# 612_jetracer_328_211.net
KiCad netlist of a schematic drawn in EAGLE
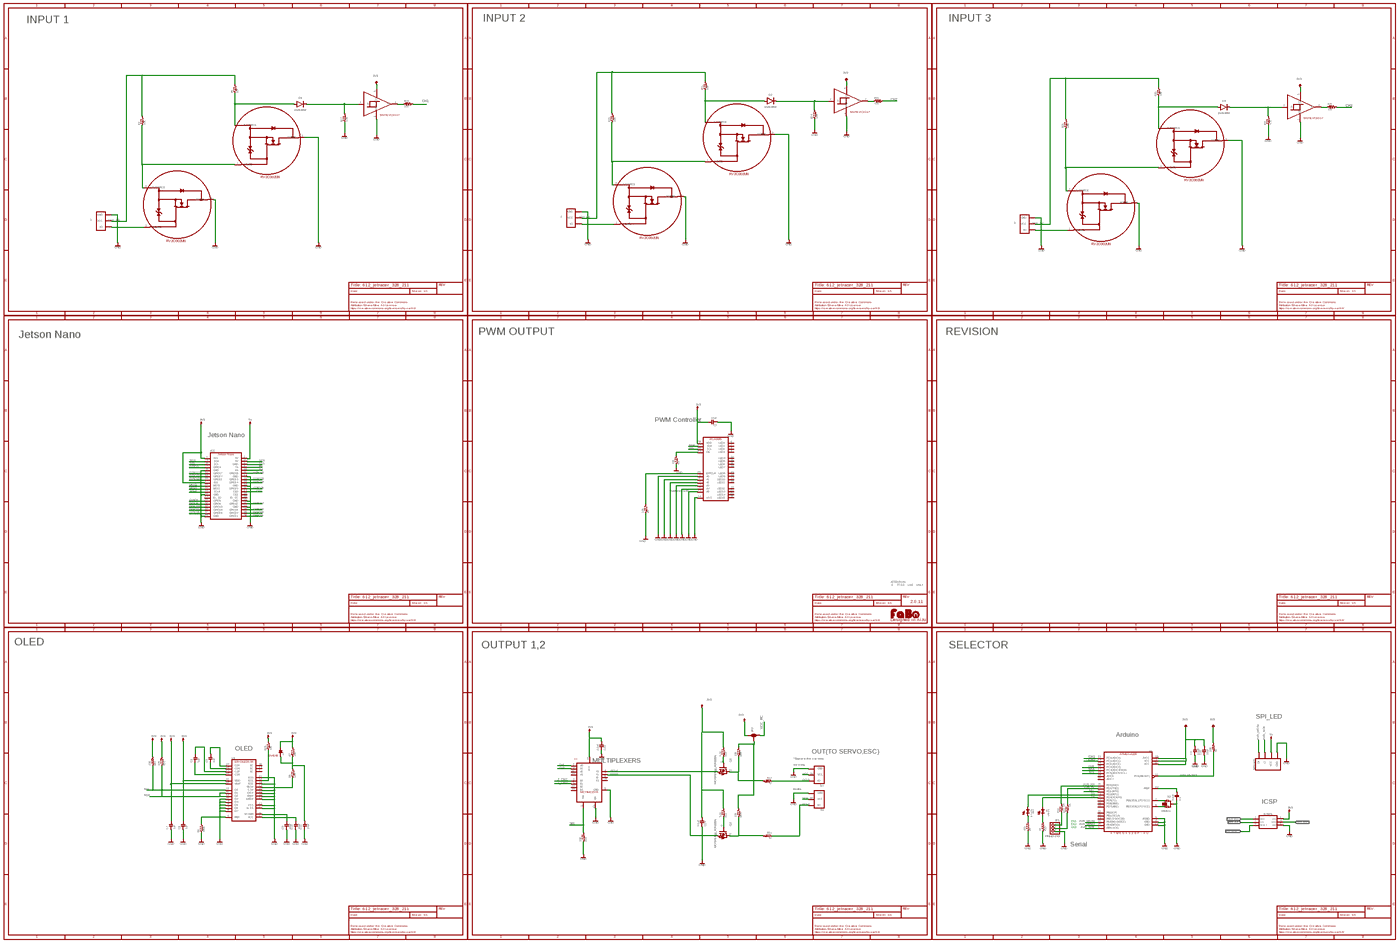
[diagram p0: schematic, sheet 1, overview]
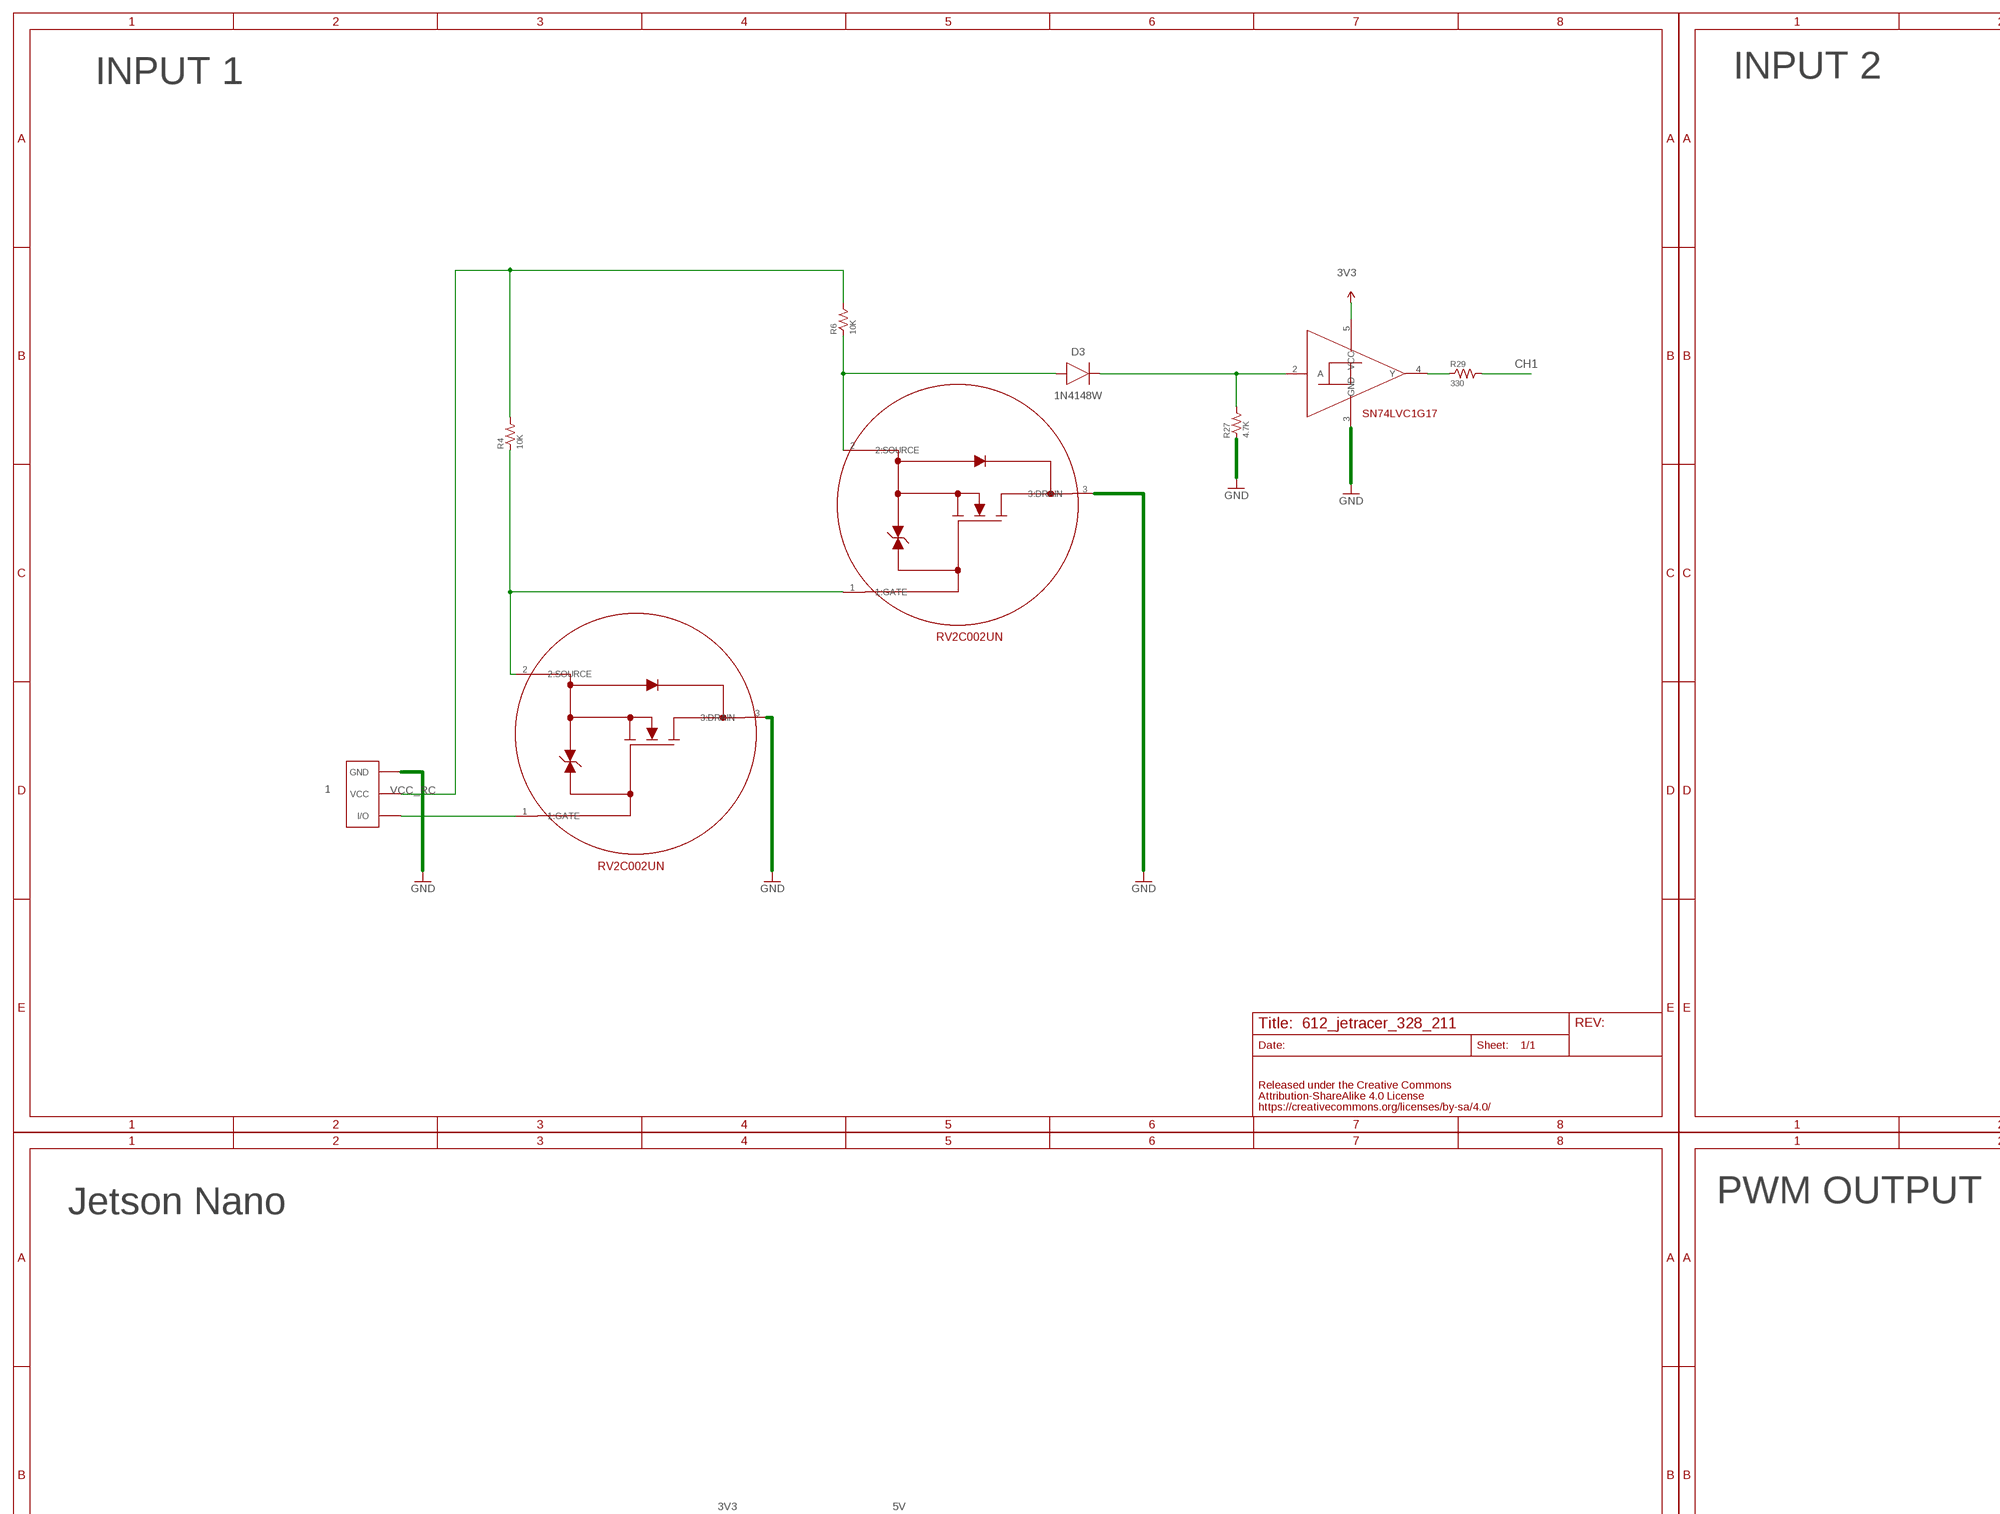
[diagram p1: schematic, sheet 1, part 1 of 6]
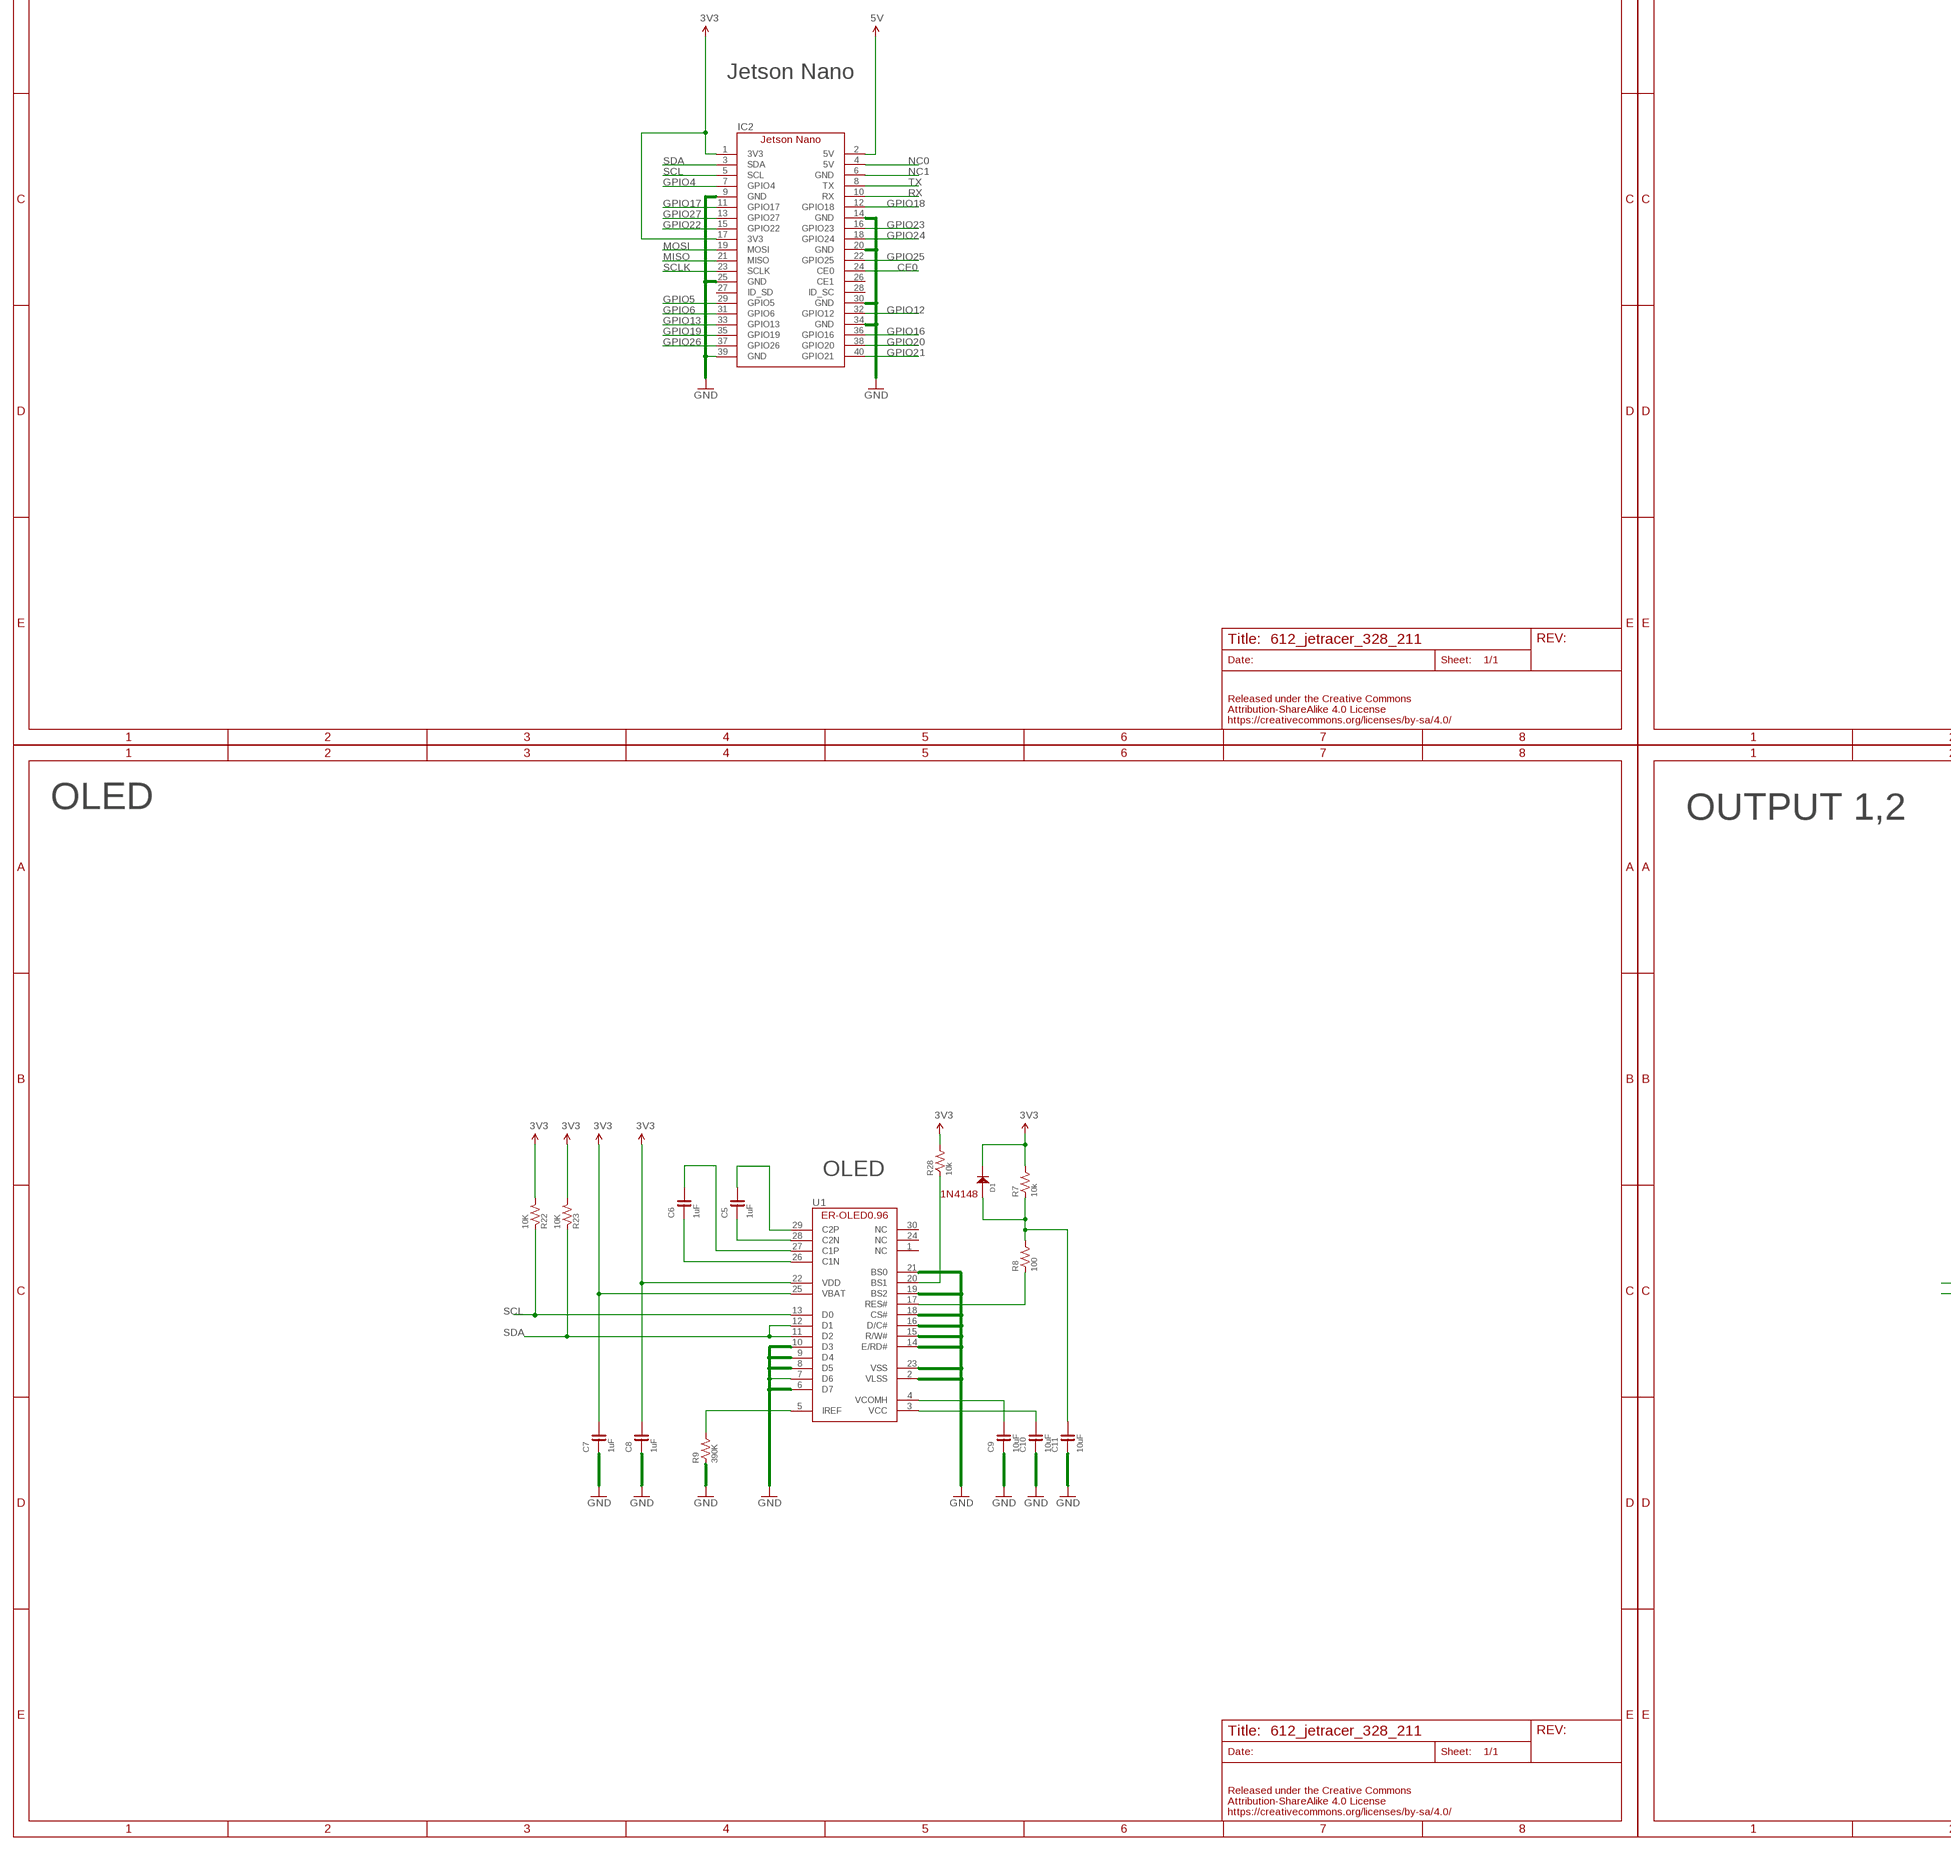
[diagram p2: schematic, sheet 1, part 2 of 6]
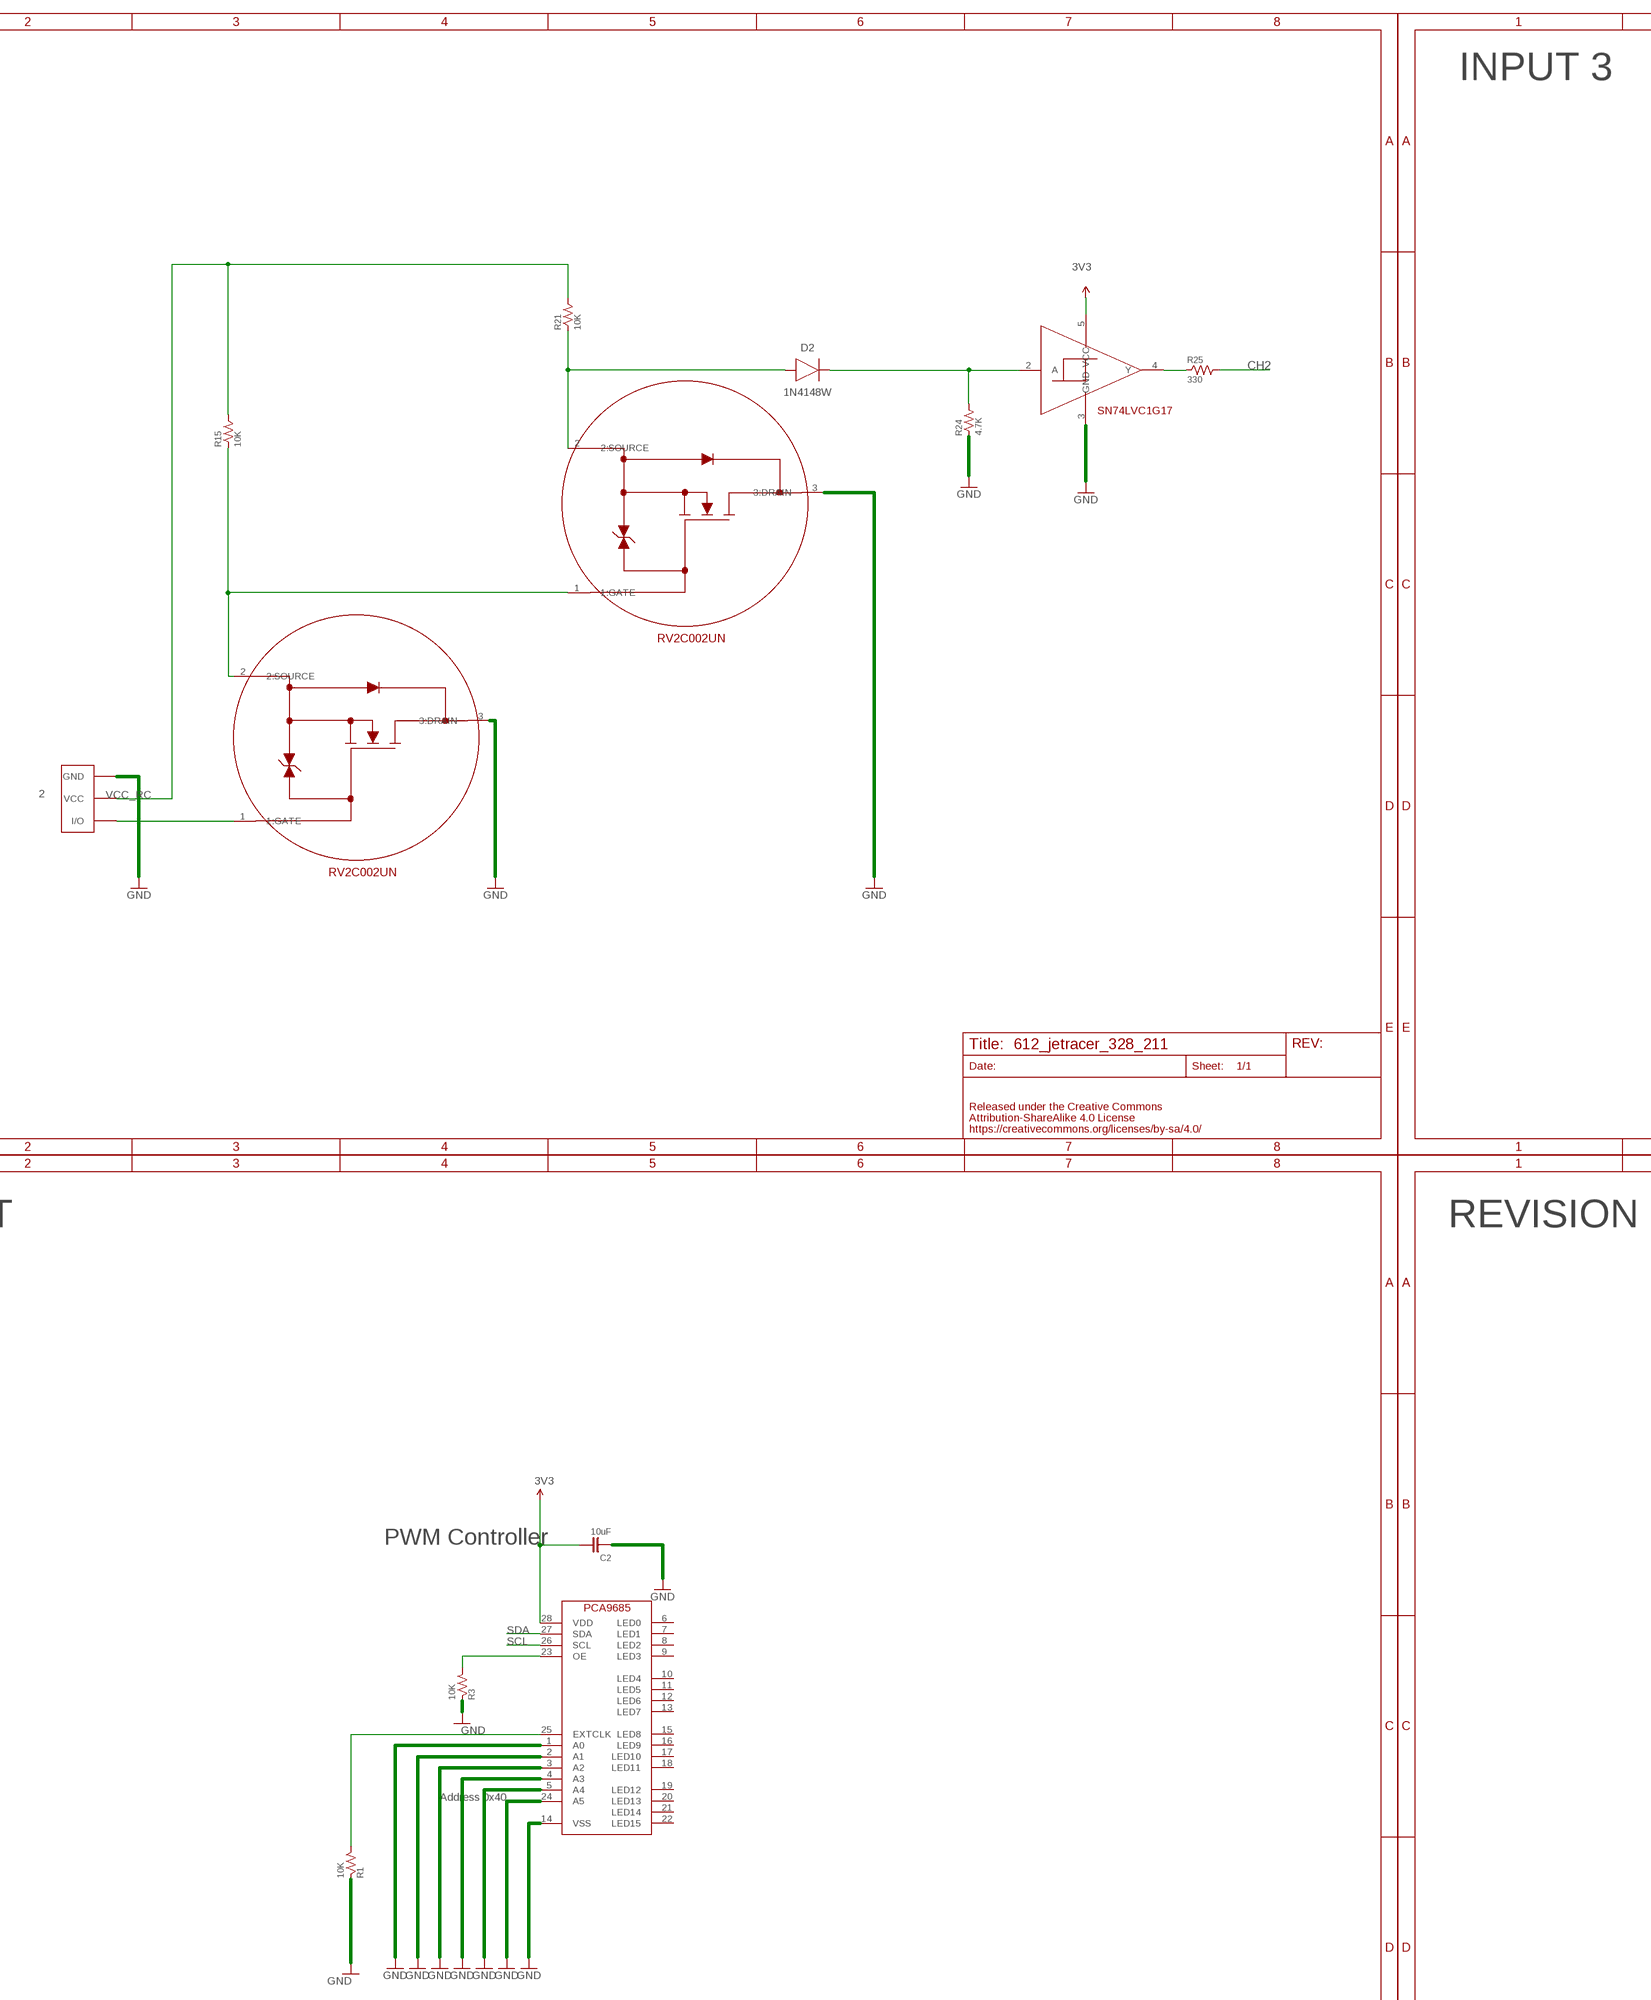
[diagram p3: schematic, sheet 1, part 3 of 6]
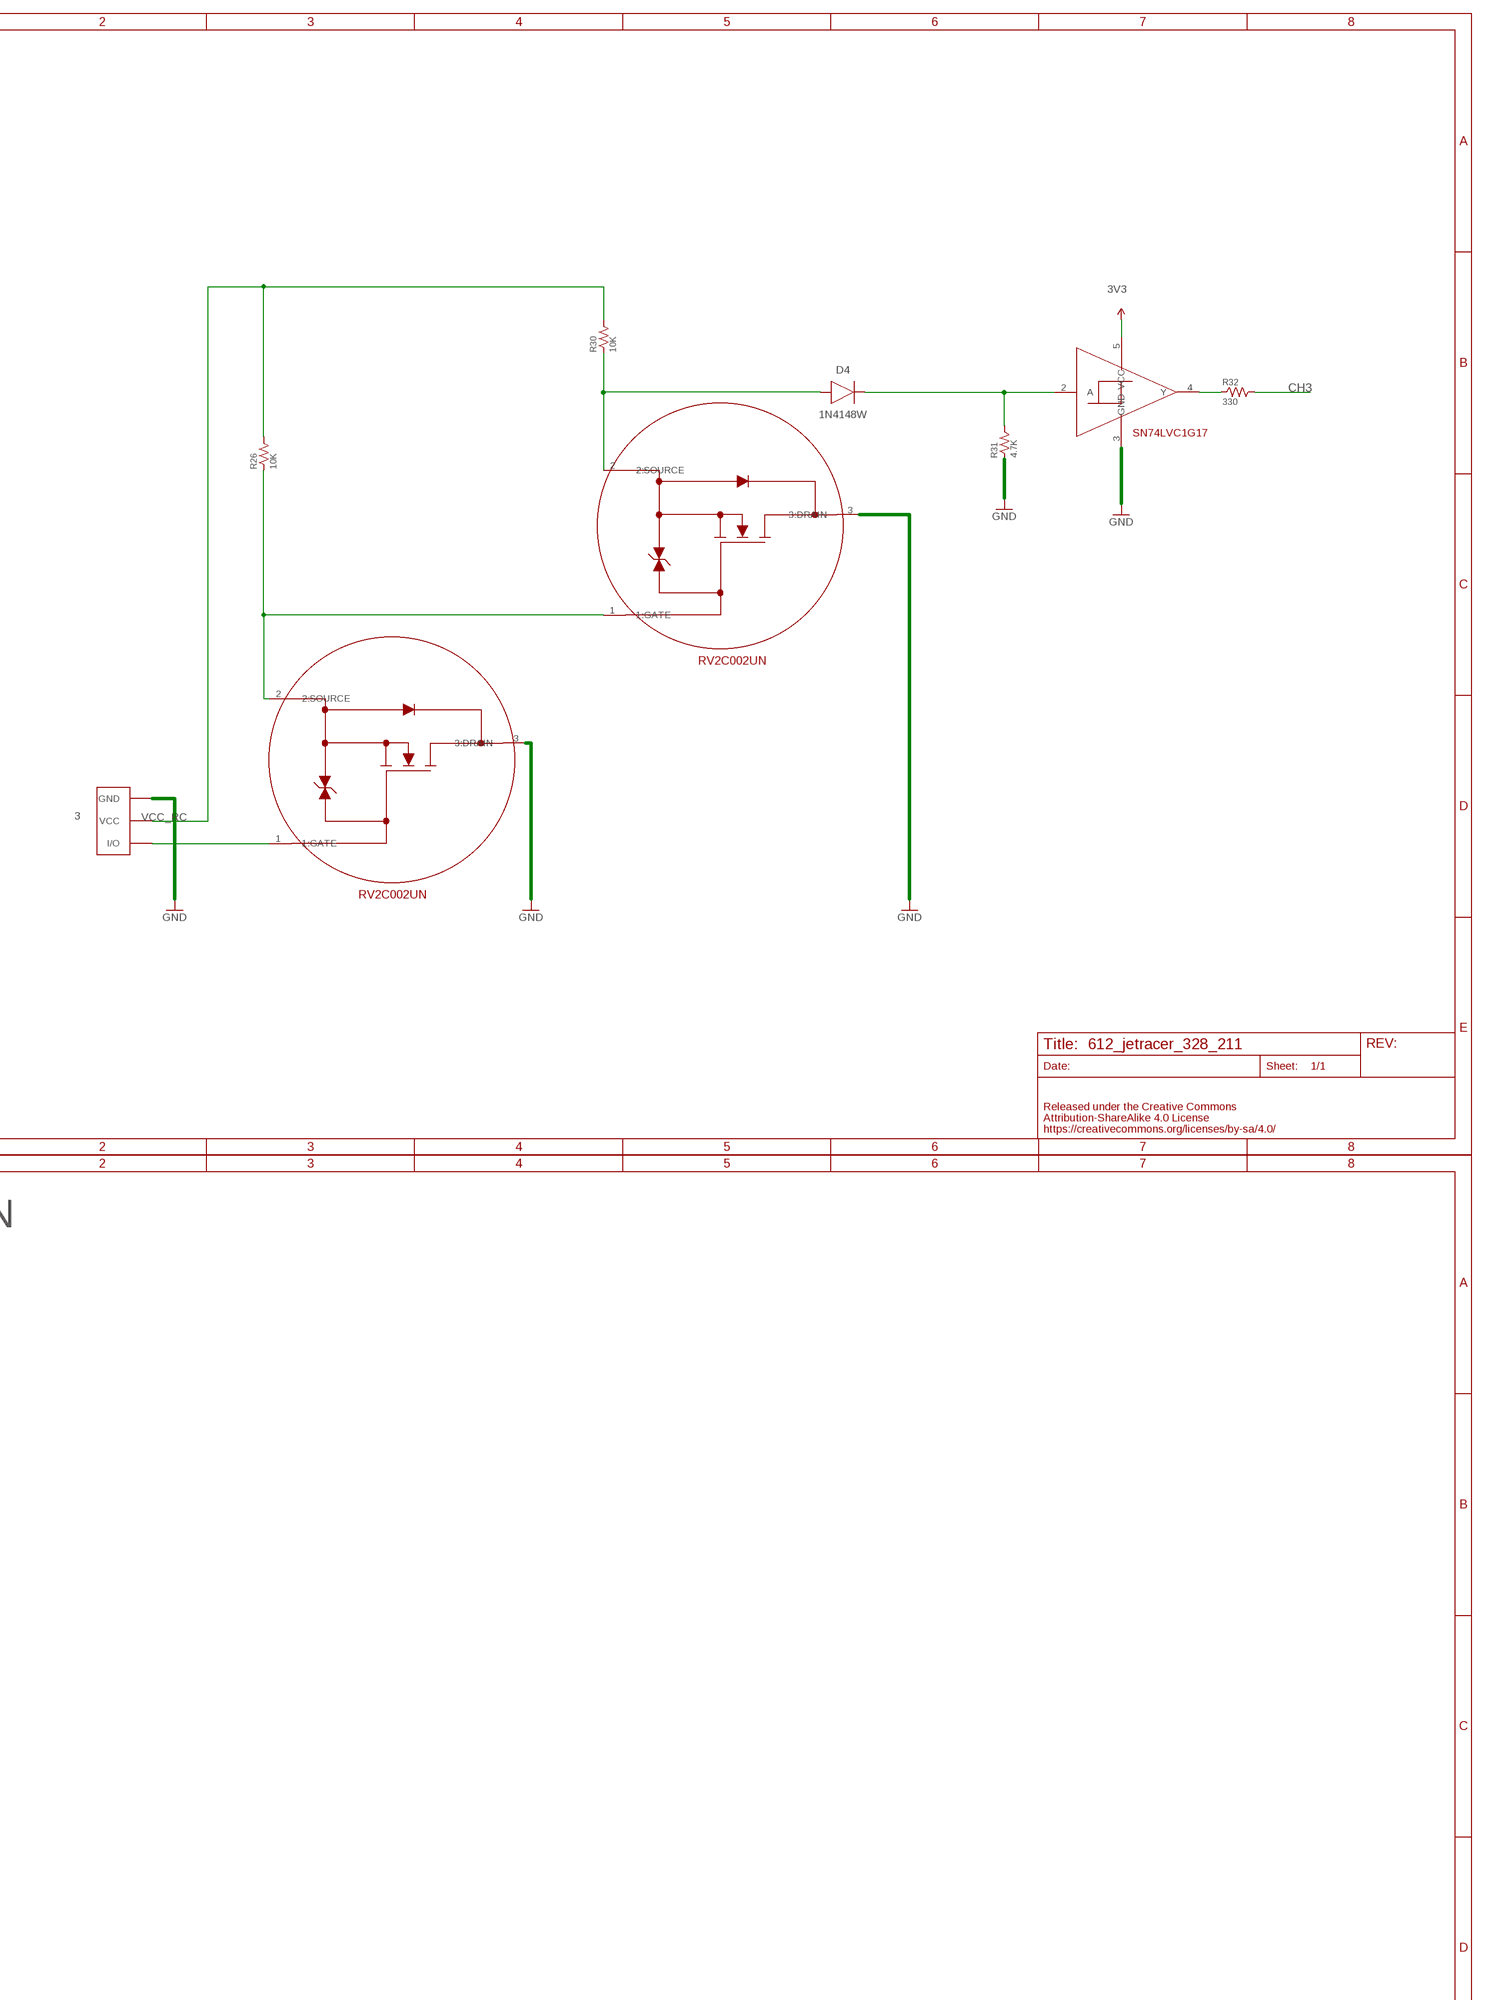
[diagram p4: schematic, sheet 1, part 4 of 6]
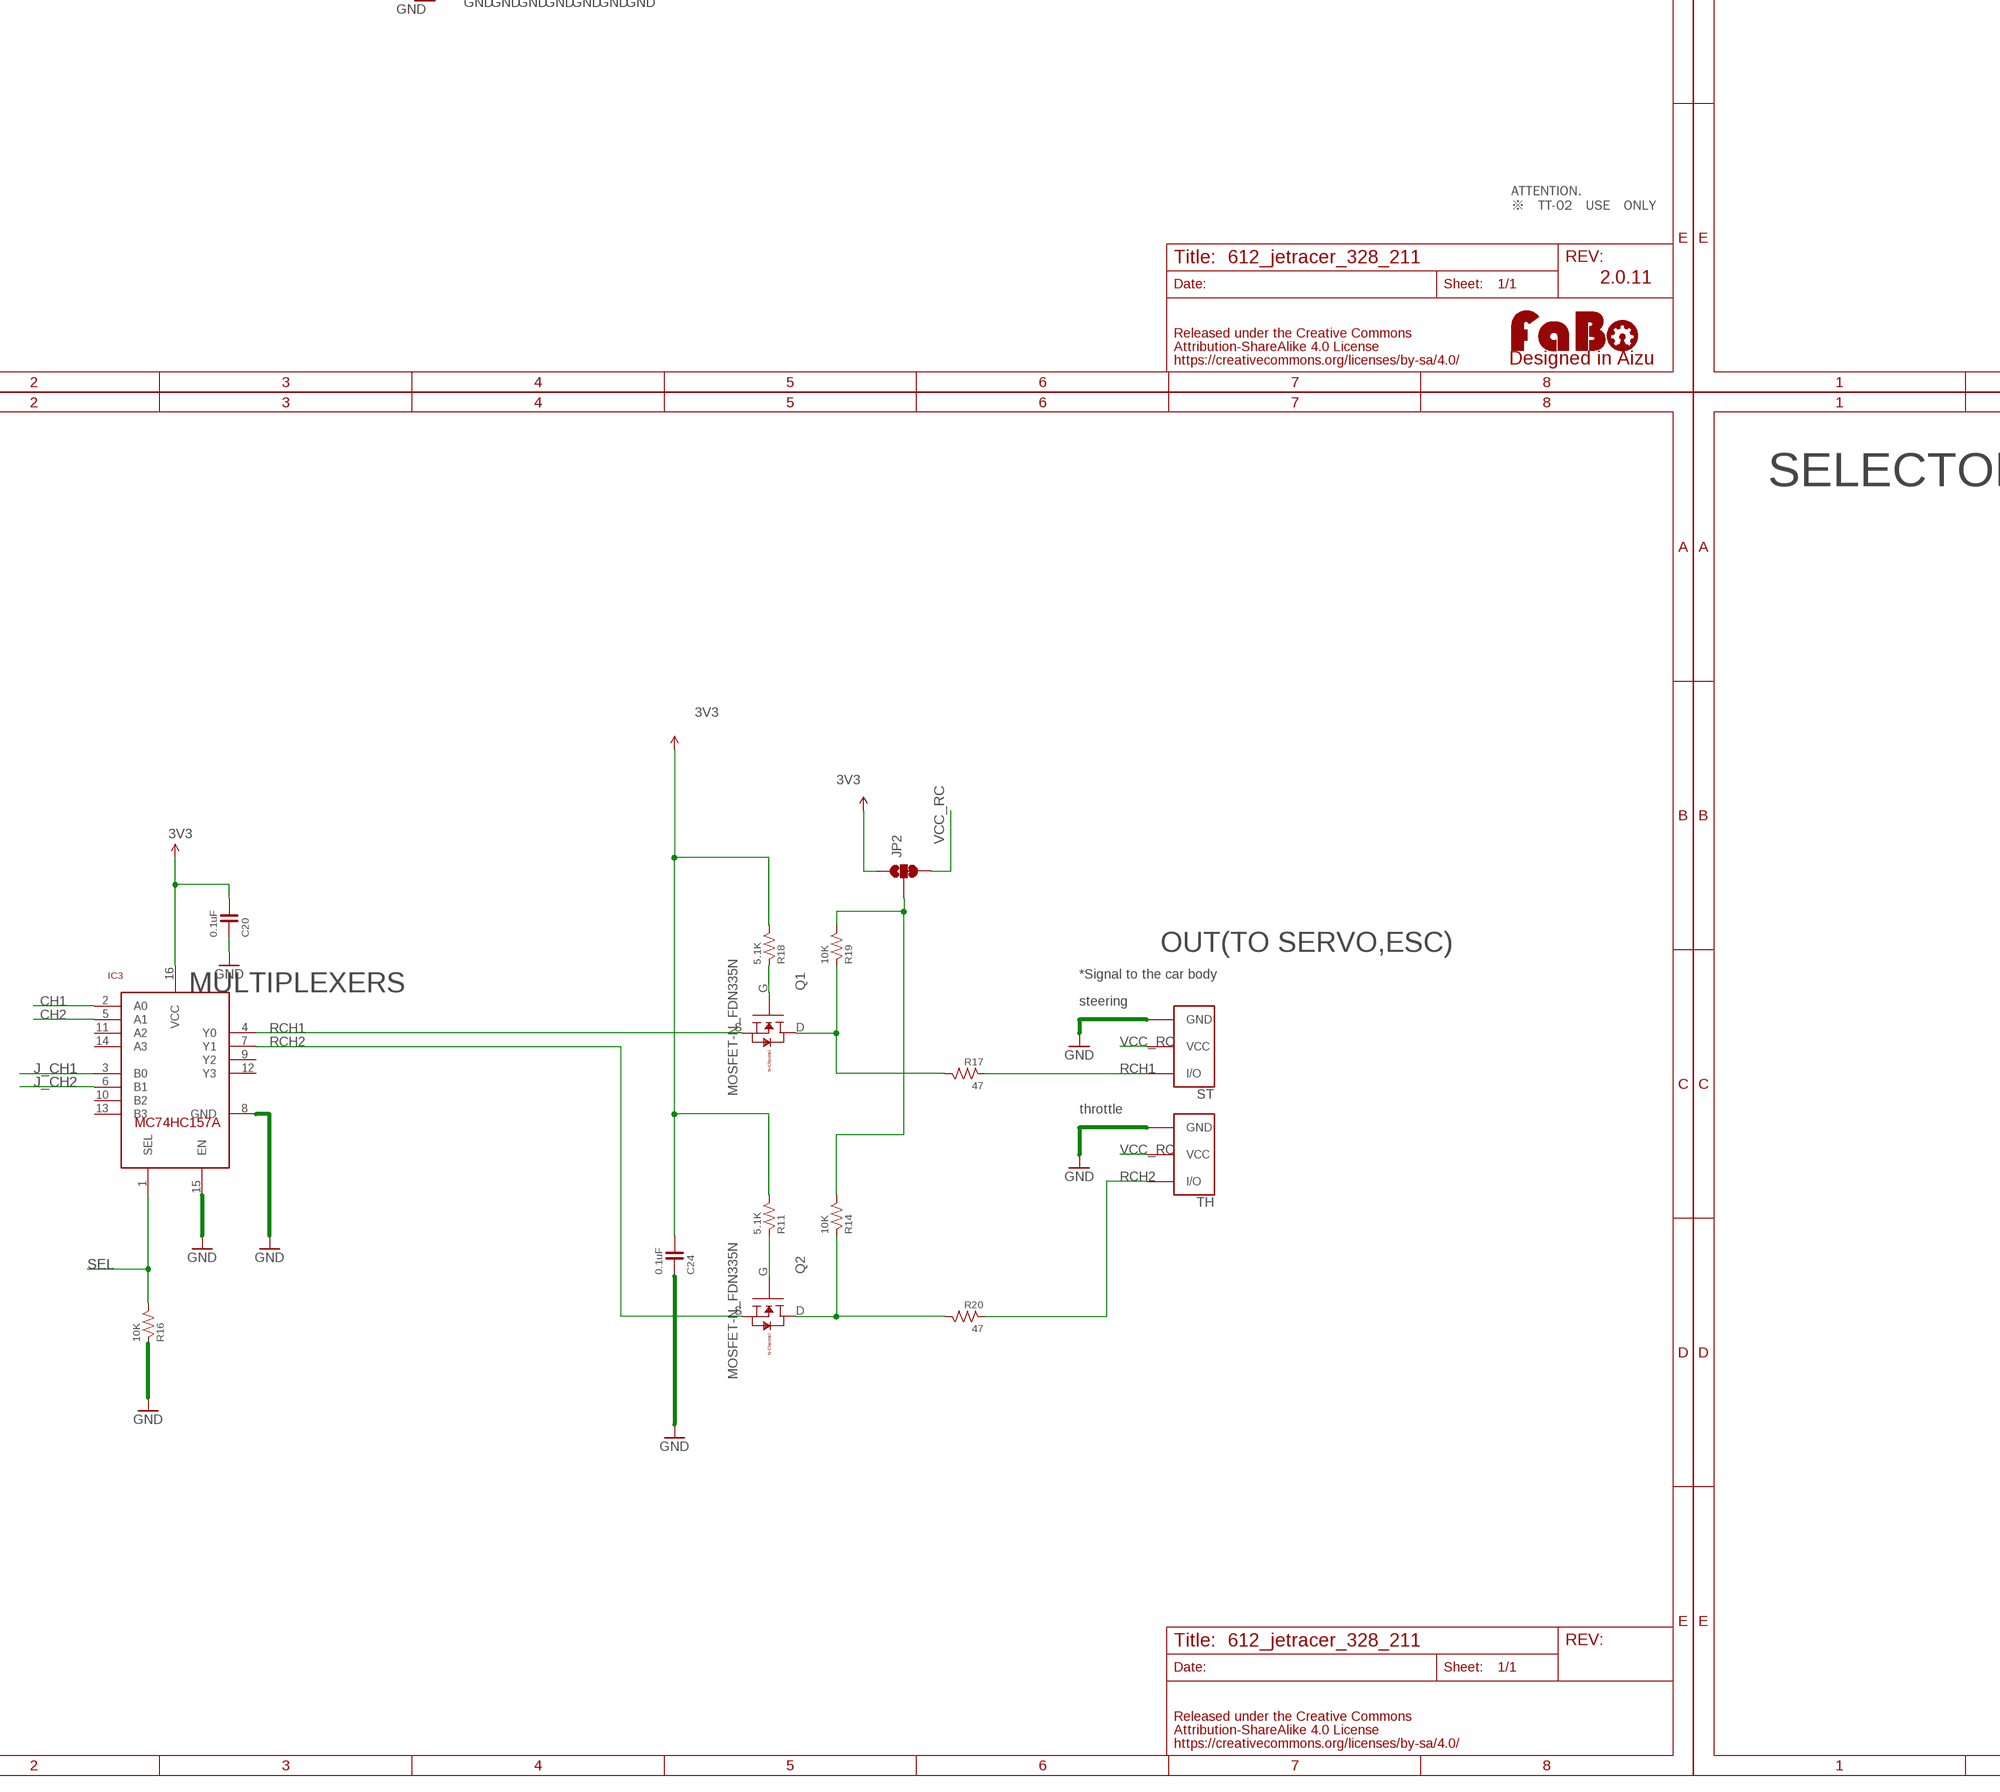
[diagram p5: schematic, sheet 1, part 5 of 6]
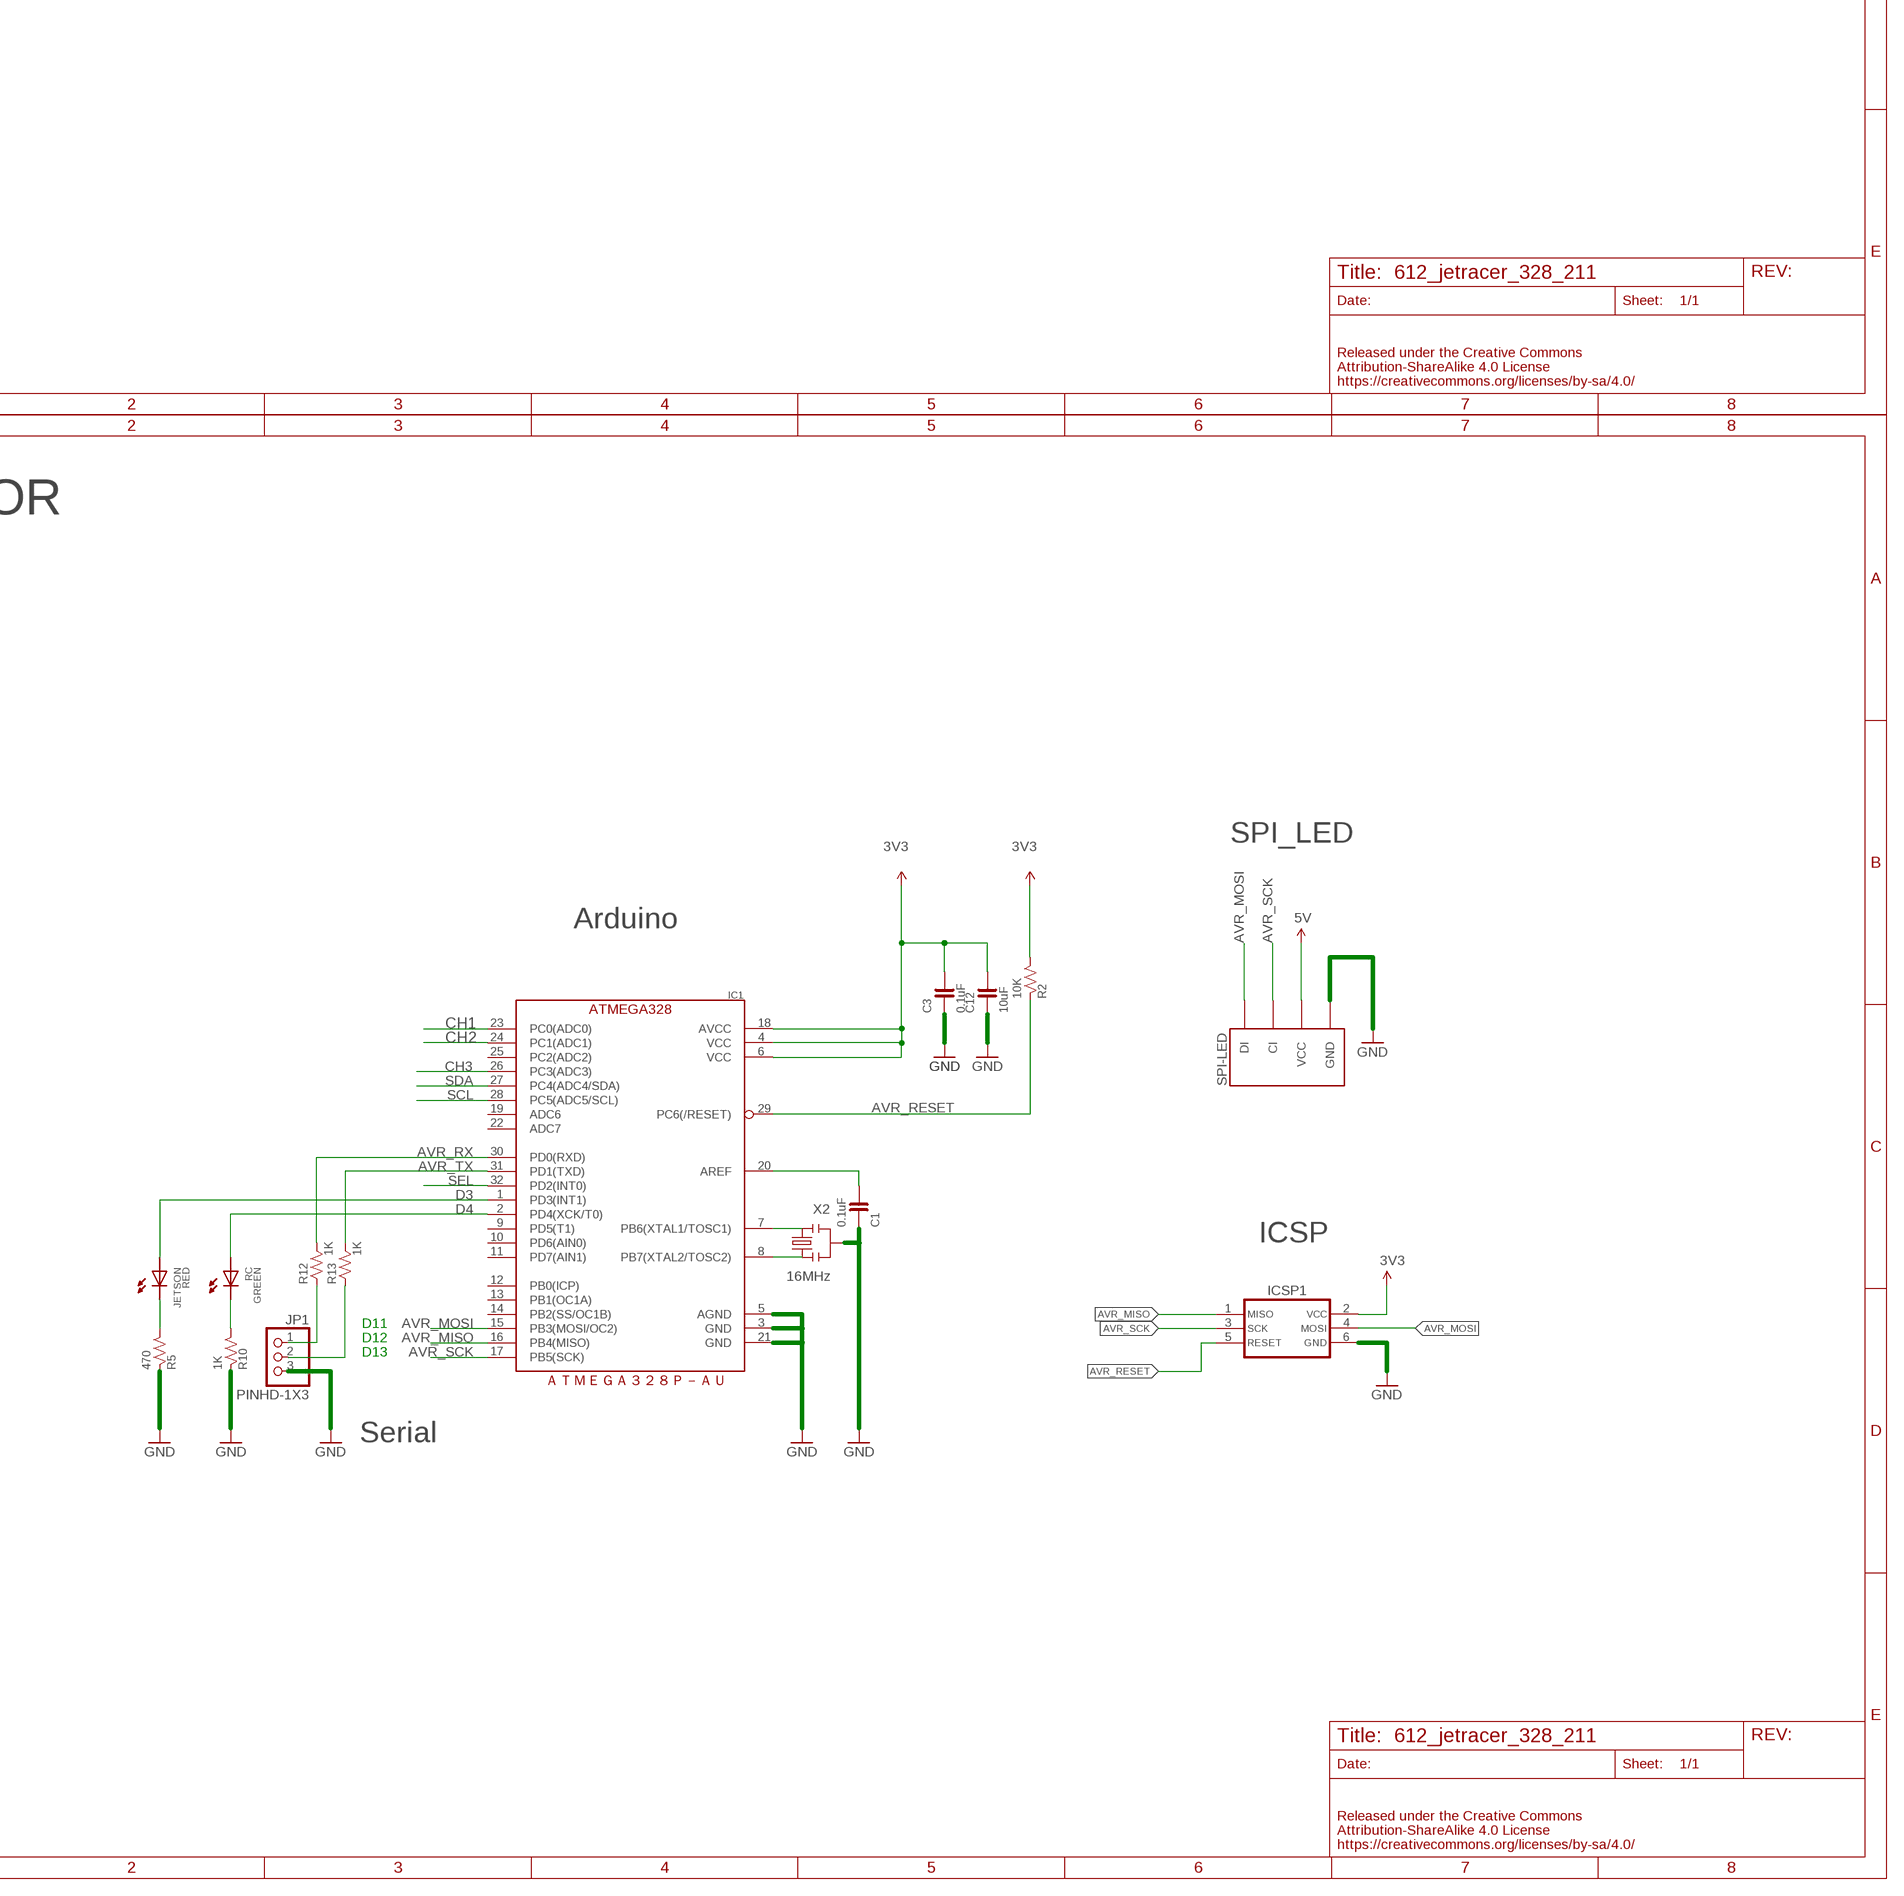
[diagram p6: schematic, sheet 1, part 6 of 6]

(export (version "E")
  (design (tool "Eeschema 10.0.6"))
  (components
    (comp (ref "1")
      (value "FABO_BRICK_3PIN-HEADER")
      (footprint "eagle-import:FABO_BRICK_3PIN_HEADER")
      (libsource (lib "eagle-import") (part "FABO_BRICK_3PIN-HEADER"))
    )
    (comp (ref "2")
      (value "FABO_BRICK_3PIN-HEADER")
      (footprint "eagle-import:FABO_BRICK_3PIN_HEADER")
      (libsource (lib "eagle-import") (part "FABO_BRICK_3PIN-HEADER"))
    )
    (comp (ref "3")
      (value "FABO_BRICK_3PIN-HEADER")
      (footprint "eagle-import:FABO_BRICK_3PIN_HEADER")
      (libsource (lib "eagle-import") (part "FABO_BRICK_3PIN-HEADER"))
    )
    (comp (ref "C1")
      (value "0.1uF")
      (footprint "eagle-import:0603")
      (libsource (lib "eagle-import") (part "CAPACITOR-0603"))
    )
    (comp (ref "C2")
      (value "10uF")
      (footprint "eagle-import:0603")
      (libsource (lib "eagle-import") (part "CAPACITOR-0603"))
    )
    (comp (ref "C3")
      (value "0.1uF")
      (footprint "eagle-import:0603-BOTTOM")
      (libsource (lib "eagle-import") (part "CAPACITOR-0603-BOTTOM"))
    )
    (comp (ref "C5")
      (value "1uF")
      (footprint "eagle-import:0603-BOTTOM")
      (libsource (lib "eagle-import") (part "CAPACITOR-0603-BOTTOM"))
    )
    (comp (ref "C6")
      (value "1uF")
      (footprint "eagle-import:0603-BOTTOM")
      (libsource (lib "eagle-import") (part "CAPACITOR-0603-BOTTOM"))
    )
    (comp (ref "C7")
      (value "1uF")
      (footprint "eagle-import:0603-BOTTOM")
      (libsource (lib "eagle-import") (part "CAPACITOR-0603-BOTTOM"))
    )
    (comp (ref "C8")
      (value "1uF")
      (footprint "eagle-import:0603-BOTTOM")
      (libsource (lib "eagle-import") (part "CAPACITOR-0603-BOTTOM"))
    )
    (comp (ref "C9")
      (value "10uF")
      (footprint "eagle-import:0603-BOTTOM")
      (libsource (lib "eagle-import") (part "CAPACITOR-0603-BOTTOM"))
    )
    (comp (ref "C10")
      (value "10uF")
      (footprint "eagle-import:0603-BOTTOM")
      (libsource (lib "eagle-import") (part "CAPACITOR-0603-BOTTOM"))
    )
    (comp (ref "C11")
      (value "10uF")
      (footprint "eagle-import:0603-BOTTOM")
      (libsource (lib "eagle-import") (part "CAPACITOR-0603-BOTTOM"))
    )
    (comp (ref "C12")
      (value "10uF")
      (footprint "eagle-import:0603-BOTTOM")
      (libsource (lib "eagle-import") (part "CAPACITOR-0603-BOTTOM"))
    )
    (comp (ref "C20")
      (value "0.1uF")
      (footprint "eagle-import:0603")
      (libsource (lib "eagle-import") (part "CAPACITOR-0603"))
    )
    (comp (ref "C24")
      (value "0.1uF")
      (footprint "eagle-import:0603")
      (fields (field (name "SPICEPREFIX") "C"))
      (libsource (lib "eagle-import") (part "CAPACITOR-0603"))
    )
    (comp (ref "D1")
      (value "1N4148")
      (footprint "eagle-import:1N4148W")
      (libsource (lib "eagle-import") (part "1N4148"))
    )
    (comp (ref "D2")
      (value "1N4148W")
      (footprint "eagle-import:SOD3715X135")
      (fields (field (name "MANUFACTURER") "Diodes Incorporated"))
      (libsource (lib "eagle-import") (part "DIODE__SOD123G1N4148W-7-F"))
    )
    (comp (ref "D3")
      (value "1N4148W")
      (footprint "eagle-import:SOD3715X135")
      (fields (field (name "MANUFACTURER") "Diodes Incorporated"))
      (libsource (lib "eagle-import") (part "DIODE__SOD123G1N4148W-7-F"))
    )
    (comp (ref "D4")
      (value "1N4148W")
      (footprint "eagle-import:SOD3715X135")
      (fields (field (name "MANUFACTURER") "Diodes Incorporated"))
      (libsource (lib "eagle-import") (part "DIODE__SOD123G1N4148W-7-F"))
    )
    (comp (ref "IC1")
      (value "ATMEGA328P-AU")
      (footprint "eagle-import:TQFP-32")
      (libsource (lib "eagle-import") (part "ATMEGA328P-AU"))
    )
    (comp (ref "IC2")
      (value "JETSON_NANO_NOBORDER")
      (footprint "eagle-import:JETSON_NANO_NOBOARDER")
      (libsource (lib "eagle-import") (part "JETSON_NANO_NOBORDER"))
    )
    (comp (ref "IC3")
      (value "MULTIPLEXERSMC74HC157A")
      (footprint "eagle-import:TSSOP-16")
      (libsource (lib "eagle-import") (part "MULTIPLEXERSMC74HC157A"))
    )
    (comp (ref "IC4")
      (value "PCA9685")
      (footprint "eagle-import:PCA9685")
      (libsource (lib "eagle-import") (part "PCA9685"))
    )
    (comp (ref "ICSP1")
      (value "ICSP_AVR-TC_NOHOLE")
      (footprint "eagle-import:TC2030")
      (libsource (lib "eagle-import") (part "ICSP_AVR-TC_NOHOLE"))
    )
    (comp (ref "JETSON")
      (value "GREEN")
      (footprint "eagle-import:0603")
      (libsource (lib "eagle-import") (part "LED-0603"))
    )
    (comp (ref "JP1")
      (value "PINHD-1X3")
      (footprint "eagle-import:1X03")
      (libsource (lib "eagle-import") (part "PINHD-1X3"))
    )
    (comp (ref "JP2")
      (value "JUMPER-SMT_3_1-NC_TRACE_SILK")
      (footprint "eagle-import:SMT-JUMPER_3_1-NC_TRACE_SILK")
      (libsource (lib "eagle-import") (part "JUMPER-SMT_3_1-NC_TRACE_SILK"))
    )
    (comp (ref "Q1")
      (value "MOSFET-N_FDN335N")
      (footprint "eagle-import:SUPERSOT-3")
      (libsource (lib "eagle-import") (part "MOSFET-N_FDN335N"))
    )
    (comp (ref "Q2")
      (value "MOSFET-N_FDN335N")
      (footprint "eagle-import:SUPERSOT-3")
      (libsource (lib "eagle-import") (part "MOSFET-N_FDN335N"))
    )
    (comp (ref "R1")
      (value "10K")
      (footprint "eagle-import:0603")
      (libsource (lib "eagle-import") (part "RESISTOR-0603"))
    )
    (comp (ref "R2")
      (value "10K")
      (footprint "eagle-import:0603")
      (libsource (lib "eagle-import") (part "RESISTOR-0603"))
    )
    (comp (ref "R3")
      (value "10K")
      (footprint "eagle-import:0603")
      (libsource (lib "eagle-import") (part "RESISTOR-0603"))
    )
    (comp (ref "R4")
      (value "10K")
      (footprint "eagle-import:0603")
      (libsource (lib "eagle-import") (part "RESISTOR-0603"))
    )
    (comp (ref "R5")
      (value "470")
      (footprint "eagle-import:0603")
      (libsource (lib "eagle-import") (part "RESISTOR-0603"))
    )
    (comp (ref "R6")
      (value "10K")
      (footprint "eagle-import:0603")
      (libsource (lib "eagle-import") (part "RESISTOR-0603"))
    )
    (comp (ref "R7")
      (value "10k")
      (footprint "eagle-import:0603-BOTTOM")
      (libsource (lib "eagle-import") (part "RESISTOR-0603-BOTTOM"))
    )
    (comp (ref "R8")
      (value "100")
      (footprint "eagle-import:0603-BOTTOM")
      (libsource (lib "eagle-import") (part "RESISTOR-0603-BOTTOM"))
    )
    (comp (ref "R9")
      (value "390K")
      (footprint "eagle-import:0603-BOTTOM")
      (libsource (lib "eagle-import") (part "RESISTOR-0603-BOTTOM"))
    )
    (comp (ref "R10")
      (value "1K")
      (footprint "eagle-import:0603")
      (libsource (lib "eagle-import") (part "RESISTOR-0603"))
    )
    (comp (ref "R11")
      (value "5.1K")
      (footprint "eagle-import:0603")
      (libsource (lib "eagle-import") (part "RESISTOR-0603"))
    )
    (comp (ref "R12")
      (value "1K")
      (footprint "eagle-import:0603")
      (libsource (lib "eagle-import") (part "RESISTOR-0603"))
    )
    (comp (ref "R13")
      (value "1K")
      (footprint "eagle-import:0603")
      (libsource (lib "eagle-import") (part "RESISTOR-0603"))
    )
    (comp (ref "R14")
      (value "10K")
      (footprint "eagle-import:0603")
      (libsource (lib "eagle-import") (part "RESISTOR-0603"))
    )
    (comp (ref "R15")
      (value "10K")
      (footprint "eagle-import:0603")
      (libsource (lib "eagle-import") (part "RESISTOR-0603"))
    )
    (comp (ref "R16")
      (value "10K")
      (footprint "eagle-import:0603")
      (libsource (lib "eagle-import") (part "RESISTOR-0603"))
    )
    (comp (ref "R17")
      (value "47")
      (footprint "eagle-import:0603")
      (libsource (lib "eagle-import") (part "RESISTOR-0603"))
    )
    (comp (ref "R18")
      (value "5.1K")
      (footprint "eagle-import:0603")
      (libsource (lib "eagle-import") (part "RESISTOR-0603"))
    )
    (comp (ref "R19")
      (value "10K")
      (footprint "eagle-import:0603")
      (libsource (lib "eagle-import") (part "RESISTOR-0603"))
    )
    (comp (ref "R20")
      (value "47")
      (footprint "eagle-import:0603")
      (libsource (lib "eagle-import") (part "RESISTOR-0603"))
    )
    (comp (ref "R21")
      (value "10K")
      (footprint "eagle-import:0603")
      (libsource (lib "eagle-import") (part "RESISTOR-0603"))
    )
    (comp (ref "R22")
      (value "10K")
      (footprint "eagle-import:0603")
      (libsource (lib "eagle-import") (part "RESISTOR-0603"))
    )
    (comp (ref "R23")
      (value "10K")
      (footprint "eagle-import:0603")
      (libsource (lib "eagle-import") (part "RESISTOR-0603"))
    )
    (comp (ref "R24")
      (value "4.7K")
      (footprint "eagle-import:0603")
      (libsource (lib "eagle-import") (part "RESISTOR-0603"))
    )
    (comp (ref "R25")
      (value "330")
      (footprint "eagle-import:0603")
      (libsource (lib "eagle-import") (part "RESISTOR-0603"))
    )
    (comp (ref "R26")
      (value "10K")
      (footprint "eagle-import:0603")
      (libsource (lib "eagle-import") (part "RESISTOR-0603"))
    )
    (comp (ref "R27")
      (value "4.7K")
      (footprint "eagle-import:0603")
      (libsource (lib "eagle-import") (part "RESISTOR-0603"))
    )
    (comp (ref "R28")
      (value "10k")
      (footprint "eagle-import:0603-BOTTOM")
      (libsource (lib "eagle-import") (part "RESISTOR-0603-BOTTOM"))
    )
    (comp (ref "R29")
      (value "330")
      (footprint "eagle-import:0603")
      (libsource (lib "eagle-import") (part "RESISTOR-0603"))
    )
    (comp (ref "R30")
      (value "10K")
      (footprint "eagle-import:0603")
      (libsource (lib "eagle-import") (part "RESISTOR-0603"))
    )
    (comp (ref "R31")
      (value "4.7K")
      (footprint "eagle-import:0603")
      (libsource (lib "eagle-import") (part "RESISTOR-0603"))
    )
    (comp (ref "R32")
      (value "330")
      (footprint "eagle-import:0603")
      (libsource (lib "eagle-import") (part "RESISTOR-0603"))
    )
    (comp (ref "RC")
      (value "RED")
      (footprint "eagle-import:0603")
      (libsource (lib "eagle-import") (part "LED-0603"))
    )
    (comp (ref "SPI-LED")
      (value "FABO-SPI-LED-B04B")
      (footprint "eagle-import:SPI-B04B-PASK-1")
      (libsource (lib "eagle-import") (part "FABO-SPI-LED-B04B"))
    )
    (comp (ref "ST")
      (value "FABO_BRICK_3PIN-HEADER")
      (footprint "eagle-import:FABO_BRICK_3PIN_HEADER")
      (libsource (lib "eagle-import") (part "FABO_BRICK_3PIN-HEADER"))
    )
    (comp (ref "TH")
      (value "FABO_BRICK_3PIN-HEADER")
      (footprint "eagle-import:FABO_BRICK_3PIN_HEADER")
      (libsource (lib "eagle-import") (part "FABO_BRICK_3PIN-HEADER"))
    )
    (comp (ref "U$1")
      (value "RV2C002UN")
      (footprint "eagle-import:DFN1006-3")
      (libsource (lib "eagle-import") (part "RV2C002UN"))
    )
    (comp (ref "U$2")
      (value "RV2C002UN")
      (footprint "eagle-import:DFN1006-3")
      (libsource (lib "eagle-import") (part "RV2C002UN"))
    )
    (comp (ref "U$3")
      (value "RV2C002UN")
      (footprint "eagle-import:DFN1006-3")
      (libsource (lib "eagle-import") (part "RV2C002UN"))
    )
    (comp (ref "U$5")
      (value "RV2C002UN")
      (footprint "eagle-import:DFN1006-3")
      (libsource (lib "eagle-import") (part "RV2C002UN"))
    )
    (comp (ref "U$6")
      (value "SN74LVC1G17")
      (footprint "eagle-import:SOT-23")
      (libsource (lib "eagle-import") (part "SN74LVC1G17"))
    )
    (comp (ref "U$7")
      (value "RV2C002UN")
      (footprint "eagle-import:DFN1006-3")
      (libsource (lib "eagle-import") (part "RV2C002UN"))
    )
    (comp (ref "U$8")
      (value "RV2C002UN")
      (footprint "eagle-import:DFN1006-3")
      (libsource (lib "eagle-import") (part "RV2C002UN"))
    )
    (comp (ref "U$9")
      (value "SN74LVC1G17")
      (footprint "eagle-import:SOT-23")
      (libsource (lib "eagle-import") (part "SN74LVC1G17"))
    )
    (comp (ref "U$11")
      (value "LOGO_FABO-M")
      (footprint "eagle-import:LOGO_FABO_MS")
      (libsource (lib "eagle-import") (part "LOGO_FABO-M"))
    )
    (comp (ref "U$14")
      (value "SN74LVC1G17")
      (footprint "eagle-import:SOT-23")
      (libsource (lib "eagle-import") (part "SN74LVC1G17"))
    )
    (comp (ref "U1")
      (value "ER-OLED0.96-1ER-CON30HT-1")
      (footprint "eagle-import:ER-CON30HT-1")
      (libsource (lib "eagle-import") (part "ER-OLED0.96-1ER-CON30HT-1"))
    )
    (comp (ref "X2")
      (value "16MHz")
      (footprint "eagle-import:CSTNE_V_C")
      (libsource (lib "eagle-import") (part "RESONATOR"))
    )
  )
  (nets
    (net (code "1") (name "/AVR_RX") (class "Default")
      (node (ref "IC1") (pin "30") (pinfunction "PD0(RXD)_30") (pintype "bidirectional"))
      (node (ref "R12") (pin "2") (pinfunction "2_2") (pintype "bidirectional"))
    )
    (net (code "2") (name "/AVR_TX") (class "Default")
      (node (ref "IC1") (pin "31") (pinfunction "PD1(TXD)_31") (pintype "bidirectional"))
      (node (ref "R13") (pin "2") (pinfunction "2_2") (pintype "bidirectional"))
    )
    (net (code "3") (name "/CE0") (class "Default")
      (node (ref "IC2") (pin "24") (pinfunction "CE0_24") (pintype "bidirectional"))
    )
    (net (code "4") (name "/CH1") (class "Default")
      (node (ref "IC1") (pin "23") (pinfunction "PC0(ADC0)_23") (pintype "bidirectional"))
      (node (ref "IC3") (pin "2") (pinfunction "A0_2") (pintype "bidirectional"))
      (node (ref "R29") (pin "2") (pinfunction "2_2") (pintype "bidirectional"))
    )
    (net (code "5") (name "/CH2") (class "Default")
      (node (ref "IC1") (pin "24") (pinfunction "PC1(ADC1)_24") (pintype "bidirectional"))
      (node (ref "IC3") (pin "5") (pinfunction "A1_5") (pintype "bidirectional"))
      (node (ref "R25") (pin "2") (pinfunction "2_2") (pintype "bidirectional"))
    )
    (net (code "6") (name "/CH3") (class "Default")
      (node (ref "IC1") (pin "26") (pinfunction "PC3(ADC3)_26") (pintype "bidirectional"))
      (node (ref "R32") (pin "2") (pinfunction "2_2") (pintype "bidirectional"))
    )
    (net (code "7") (name "/D3") (class "Default")
      (node (ref "IC1") (pin "1") (pinfunction "PD3(INT1)_1") (pintype "bidirectional"))
      (node (ref "RC") (pin "ANODE") (pinfunction "ANODE_ANODE") (pintype "passive"))
    )
    (net (code "8") (name "/D4") (class "Default")
      (node (ref "IC1") (pin "2") (pinfunction "PD4(XCK/T0)_2") (pintype "bidirectional"))
      (node (ref "JETSON") (pin "ANODE") (pinfunction "ANODE_ANODE") (pintype "passive"))
    )
    (net (code "9") (name "/GPIO4") (class "Default")
      (node (ref "IC2") (pin "7") (pinfunction "GPIO4_7") (pintype "bidirectional"))
    )
    (net (code "10") (name "/GPIO5") (class "Default")
      (node (ref "IC2") (pin "29") (pinfunction "GPIO5_29") (pintype "bidirectional"))
    )
    (net (code "11") (name "/GPIO6") (class "Default")
      (node (ref "IC2") (pin "31") (pinfunction "GPIO6_31") (pintype "bidirectional"))
    )
    (net (code "12") (name "/GPIO12") (class "Default")
      (node (ref "IC2") (pin "32") (pinfunction "GPIO12_32") (pintype "bidirectional"))
    )
    (net (code "13") (name "/GPIO13") (class "Default")
      (node (ref "IC2") (pin "33") (pinfunction "GPIO13_33") (pintype "bidirectional"))
    )
    (net (code "14") (name "/GPIO16") (class "Default")
      (node (ref "IC2") (pin "36") (pinfunction "GPIO16_36") (pintype "bidirectional"))
    )
    (net (code "15") (name "/GPIO17") (class "Default")
      (node (ref "IC2") (pin "11") (pinfunction "GPIO17_11") (pintype "bidirectional"))
    )
    (net (code "16") (name "/GPIO18") (class "Default")
      (node (ref "IC2") (pin "12") (pinfunction "GPIO18_12") (pintype "bidirectional"))
    )
    (net (code "17") (name "/GPIO19") (class "Default")
      (node (ref "IC2") (pin "35") (pinfunction "GPIO19_35") (pintype "bidirectional"))
    )
    (net (code "18") (name "/GPIO20") (class "Default")
      (node (ref "IC2") (pin "38") (pinfunction "GPIO20_38") (pintype "bidirectional"))
    )
    (net (code "19") (name "/GPIO21") (class "Default")
      (node (ref "IC2") (pin "40") (pinfunction "GPIO21_40") (pintype "bidirectional"))
    )
    (net (code "20") (name "/GPIO22") (class "Default")
      (node (ref "IC2") (pin "15") (pinfunction "GPIO22_15") (pintype "bidirectional"))
    )
    (net (code "21") (name "/GPIO23") (class "Default")
      (node (ref "IC2") (pin "16") (pinfunction "GPIO23_16") (pintype "bidirectional"))
    )
    (net (code "22") (name "/GPIO24") (class "Default")
      (node (ref "IC2") (pin "18") (pinfunction "GPIO24_18") (pintype "bidirectional"))
    )
    (net (code "23") (name "/GPIO25") (class "Default")
      (node (ref "IC2") (pin "22") (pinfunction "GPIO25_22") (pintype "bidirectional"))
    )
    (net (code "24") (name "/GPIO26") (class "Default")
      (node (ref "IC2") (pin "37") (pinfunction "GPIO26_37") (pintype "bidirectional"))
    )
    (net (code "25") (name "/GPIO27") (class "Default")
      (node (ref "IC2") (pin "13") (pinfunction "GPIO27_13") (pintype "bidirectional"))
    )
    (net (code "26") (name "/J_CH1") (class "Default")
      (node (ref "IC3") (pin "3") (pinfunction "B0_3") (pintype "bidirectional"))
    )
    (net (code "27") (name "/J_CH2") (class "Default")
      (node (ref "IC3") (pin "6") (pinfunction "B1_6") (pintype "bidirectional"))
    )
    (net (code "28") (name "/MISO") (class "Default")
      (node (ref "IC2") (pin "21") (pinfunction "MISO_21") (pintype "bidirectional"))
    )
    (net (code "29") (name "/MOSI") (class "Default")
      (node (ref "IC2") (pin "19") (pinfunction "MOSI_19") (pintype "bidirectional"))
    )
    (net (code "30") (name "/NC0") (class "Default")
      (node (ref "IC2") (pin "4") (pinfunction "5V_4") (pintype "bidirectional"))
    )
    (net (code "31") (name "/NC1") (class "Default")
      (node (ref "IC2") (pin "6") (pinfunction "GND_6") (pintype "bidirectional"))
    )
    (net (code "32") (name "/RCH1") (class "Default")
      (node (ref "IC3") (pin "4") (pinfunction "Y0_4") (pintype "bidirectional"))
      (node (ref "Q1") (pin "S") (pinfunction "S_S") (pintype "passive"))
    )
    (net (code "33") (name "/RCH2") (class "Default")
      (node (ref "IC3") (pin "7") (pinfunction "Y1_7") (pintype "bidirectional"))
      (node (ref "Q2") (pin "S") (pinfunction "S_S") (pintype "passive"))
    )
    (net (code "34") (name "/RX") (class "Default")
      (node (ref "IC2") (pin "10") (pinfunction "RX_10") (pintype "bidirectional"))
    )
    (net (code "35") (name "/SCL") (class "Default")
      (node (ref "IC1") (pin "28") (pinfunction "PC5(ADC5/SCL)_28") (pintype "bidirectional"))
      (node (ref "IC2") (pin "5") (pinfunction "SCL_5") (pintype "bidirectional"))
      (node (ref "IC4") (pin "26") (pinfunction "SCL_26") (pintype "bidirectional"))
      (node (ref "R22") (pin "1") (pinfunction "1_1") (pintype "bidirectional"))
      (node (ref "U1") (pin "13") (pinfunction "D0_13") (pintype "bidirectional"))
    )
    (net (code "36") (name "/SCLK") (class "Default")
      (node (ref "IC2") (pin "23") (pinfunction "SCLK_23") (pintype "bidirectional"))
    )
    (net (code "37") (name "/SDA") (class "Default")
      (node (ref "IC1") (pin "27") (pinfunction "PC4(ADC4/SDA)_27") (pintype "bidirectional"))
      (node (ref "IC2") (pin "3") (pinfunction "SDA_3") (pintype "bidirectional"))
      (node (ref "IC4") (pin "27") (pinfunction "SDA_27") (pintype "bidirectional"))
      (node (ref "R23") (pin "1") (pinfunction "1_1") (pintype "bidirectional"))
      (node (ref "U1") (pin "11") (pinfunction "D2_11") (pintype "bidirectional"))
      (node (ref "U1") (pin "12") (pinfunction "D1_12") (pintype "bidirectional"))
    )
    (net (code "38") (name "/SEL") (class "Default")
      (node (ref "IC1") (pin "32") (pinfunction "PD2(INT0)_32") (pintype "bidirectional"))
      (node (ref "IC3") (pin "1") (pinfunction "SEL_1") (pintype "bidirectional"))
      (node (ref "R16") (pin "2") (pinfunction "2_2") (pintype "bidirectional"))
    )
    (net (code "39") (name "/TX") (class "Default")
      (node (ref "IC2") (pin "8") (pinfunction "TX_8") (pintype "bidirectional"))
    )
    (net (code "40") (name "/VCC_RC") (class "Default")
      (node (ref "1") (pin "VCC") (pinfunction "VCC_VCC") (pintype "bidirectional"))
      (node (ref "2") (pin "VCC") (pinfunction "VCC_VCC") (pintype "bidirectional"))
      (node (ref "3") (pin "VCC") (pinfunction "VCC_VCC") (pintype "bidirectional"))
      (node (ref "JP2") (pin "3") (pinfunction "3_3") (pintype "passive"))
      (node (ref "R15") (pin "2") (pinfunction "2_2") (pintype "bidirectional"))
      (node (ref "R21") (pin "2") (pinfunction "2_2") (pintype "bidirectional"))
      (node (ref "R26") (pin "2") (pinfunction "2_2") (pintype "bidirectional"))
      (node (ref "R30") (pin "2") (pinfunction "2_2") (pintype "bidirectional"))
      (node (ref "R4") (pin "2") (pinfunction "2_2") (pintype "bidirectional"))
      (node (ref "R6") (pin "2") (pinfunction "2_2") (pintype "bidirectional"))
      (node (ref "ST") (pin "VCC") (pinfunction "VCC_VCC") (pintype "bidirectional"))
      (node (ref "TH") (pin "VCC") (pinfunction "VCC_VCC") (pintype "bidirectional"))
    )
    (net (code "41") (name "3V3") (class "Default")
      (node (ref "C12") (pin "2") (pinfunction "2_2") (pintype "passive"))
      (node (ref "C2") (pin "2") (pinfunction "2_2") (pintype "passive"))
      (node (ref "C20") (pin "2") (pinfunction "2_2") (pintype "passive"))
      (node (ref "C24") (pin "2") (pinfunction "2_2") (pintype "passive"))
      (node (ref "C3") (pin "2") (pinfunction "2_2") (pintype "passive"))
      (node (ref "C7") (pin "2") (pinfunction "2_2") (pintype "passive"))
      (node (ref "C8") (pin "2") (pinfunction "2_2") (pintype "passive"))
      (node (ref "D1") (pin "CATHODE") (pinfunction "CATHODE_CATHODE") (pintype "bidirectional"))
      (node (ref "IC1") (pin "18") (pinfunction "AVCC_18") (pintype "bidirectional"))
      (node (ref "IC1") (pin "4") (pinfunction "VCC_4") (pintype "bidirectional"))
      (node (ref "IC1") (pin "6") (pinfunction "VCC_6") (pintype "bidirectional"))
      (node (ref "IC2") (pin "1") (pinfunction "3V3_1") (pintype "bidirectional"))
      (node (ref "IC2") (pin "17") (pinfunction "3V3_17") (pintype "bidirectional"))
      (node (ref "IC3") (pin "16") (pinfunction "VCC_16") (pintype "bidirectional"))
      (node (ref "IC4") (pin "28") (pinfunction "VDD_28") (pintype "bidirectional"))
      (node (ref "ICSP1") (pin "2") (pinfunction "2_2") (pintype "passive"))
      (node (ref "JP2") (pin "1") (pinfunction "1_1") (pintype "passive"))
      (node (ref "R11") (pin "2") (pinfunction "2_2") (pintype "bidirectional"))
      (node (ref "R18") (pin "2") (pinfunction "2_2") (pintype "bidirectional"))
      (node (ref "R2") (pin "2") (pinfunction "2_2") (pintype "bidirectional"))
      (node (ref "R22") (pin "2") (pinfunction "2_2") (pintype "bidirectional"))
      (node (ref "R23") (pin "2") (pinfunction "2_2") (pintype "bidirectional"))
      (node (ref "R28") (pin "2") (pinfunction "2_2") (pintype "bidirectional"))
      (node (ref "R7") (pin "2") (pinfunction "2_2") (pintype "bidirectional"))
      (node (ref "U$14") (pin "5") (pinfunction "VCC_5") (pintype "bidirectional"))
      (node (ref "U$6") (pin "5") (pinfunction "VCC_5") (pintype "bidirectional"))
      (node (ref "U$9") (pin "5") (pinfunction "VCC_5") (pintype "bidirectional"))
      (node (ref "U1") (pin "22") (pinfunction "VDD_22") (pintype "bidirectional"))
      (node (ref "U1") (pin "25") (pinfunction "VBAT_25") (pintype "bidirectional"))
    )
    (net (code "42") (name "5V") (class "Default")
      (node (ref "IC2") (pin "2") (pinfunction "5V_2") (pintype "bidirectional"))
      (node (ref "SPI-LED") (pin "VCC") (pinfunction "VCC_VCC") (pintype "bidirectional"))
    )
    (net (code "43") (name "AVR_MISO") (class "Default")
      (node (ref "IC1") (pin "16") (pinfunction "PB4(MISO)_16") (pintype "bidirectional"))
      (node (ref "ICSP1") (pin "1") (pinfunction "1_1") (pintype "passive"))
    )
    (net (code "44") (name "AVR_MOSI") (class "Default")
      (node (ref "IC1") (pin "15") (pinfunction "PB3(MOSI/OC2)_15") (pintype "bidirectional"))
      (node (ref "ICSP1") (pin "4") (pinfunction "4_4") (pintype "passive"))
      (node (ref "SPI-LED") (pin "DI") (pinfunction "DI_DI") (pintype "bidirectional"))
    )
    (net (code "45") (name "AVR_RESET") (class "Default")
      (node (ref "IC1") (pin "29") (pinfunction "PC6(/RESET)_29") (pintype "bidirectional"))
      (node (ref "ICSP1") (pin "5") (pinfunction "5_5") (pintype "passive"))
      (node (ref "R2") (pin "1") (pinfunction "1_1") (pintype "bidirectional"))
    )
    (net (code "46") (name "AVR_SCK") (class "Default")
      (node (ref "IC1") (pin "17") (pinfunction "PB5(SCK)_17") (pintype "bidirectional"))
      (node (ref "ICSP1") (pin "3") (pinfunction "3_3") (pintype "passive"))
      (node (ref "SPI-LED") (pin "CI") (pinfunction "CI_CI") (pintype "bidirectional"))
    )
    (net (code "47") (name "GND") (class "Default")
      (node (ref "1") (pin "GND") (pinfunction "GND_GND") (pintype "bidirectional"))
      (node (ref "2") (pin "GND") (pinfunction "GND_GND") (pintype "bidirectional"))
      (node (ref "3") (pin "GND") (pinfunction "GND_GND") (pintype "bidirectional"))
      (node (ref "C1") (pin "1") (pinfunction "1_1") (pintype "passive"))
      (node (ref "C10") (pin "1") (pinfunction "1_1") (pintype "passive"))
      (node (ref "C11") (pin "1") (pinfunction "1_1") (pintype "passive"))
      (node (ref "C12") (pin "1") (pinfunction "1_1") (pintype "passive"))
      (node (ref "C2") (pin "1") (pinfunction "1_1") (pintype "passive"))
      (node (ref "C20") (pin "1") (pinfunction "1_1") (pintype "passive"))
      (node (ref "C24") (pin "1") (pinfunction "1_1") (pintype "passive"))
      (node (ref "C3") (pin "1") (pinfunction "1_1") (pintype "passive"))
      (node (ref "C7") (pin "1") (pinfunction "1_1") (pintype "passive"))
      (node (ref "C8") (pin "1") (pinfunction "1_1") (pintype "passive"))
      (node (ref "C9") (pin "1") (pinfunction "1_1") (pintype "passive"))
      (node (ref "IC1") (pin "21") (pinfunction "GND_21") (pintype "bidirectional"))
      (node (ref "IC1") (pin "3") (pinfunction "GND_3") (pintype "bidirectional"))
      (node (ref "IC1") (pin "5") (pinfunction "AGND_5") (pintype "bidirectional"))
      (node (ref "IC2") (pin "14") (pinfunction "GND_14") (pintype "bidirectional"))
      (node (ref "IC2") (pin "20") (pinfunction "GND_20") (pintype "bidirectional"))
      (node (ref "IC2") (pin "25") (pinfunction "GND_25") (pintype "bidirectional"))
      (node (ref "IC2") (pin "30") (pinfunction "GND_30") (pintype "bidirectional"))
      (node (ref "IC2") (pin "34") (pinfunction "GND_34") (pintype "bidirectional"))
      (node (ref "IC2") (pin "39") (pinfunction "GND_39") (pintype "bidirectional"))
      (node (ref "IC2") (pin "9") (pinfunction "GND_9") (pintype "bidirectional"))
      (node (ref "IC3") (pin "15") (pinfunction "EN_15") (pintype "bidirectional"))
      (node (ref "IC3") (pin "8") (pinfunction "GND_8") (pintype "bidirectional"))
      (node (ref "IC4") (pin "1") (pinfunction "A0_1") (pintype "bidirectional"))
      (node (ref "IC4") (pin "14") (pinfunction "VSS_14") (pintype "bidirectional"))
      (node (ref "IC4") (pin "2") (pinfunction "A1_2") (pintype "bidirectional"))
      (node (ref "IC4") (pin "24") (pinfunction "A5_24") (pintype "bidirectional"))
      (node (ref "IC4") (pin "3") (pinfunction "A2_3") (pintype "bidirectional"))
      (node (ref "IC4") (pin "4") (pinfunction "A3_4") (pintype "bidirectional"))
      (node (ref "IC4") (pin "5") (pinfunction "A4_5") (pintype "bidirectional"))
      (node (ref "ICSP1") (pin "6") (pinfunction "6_6") (pintype "passive"))
      (node (ref "JP1") (pin "3") (pinfunction "3_3") (pintype "passive"))
      (node (ref "R1") (pin "1") (pinfunction "1_1") (pintype "bidirectional"))
      (node (ref "R10") (pin "1") (pinfunction "1_1") (pintype "bidirectional"))
      (node (ref "R16") (pin "1") (pinfunction "1_1") (pintype "bidirectional"))
      (node (ref "R24") (pin "1") (pinfunction "1_1") (pintype "bidirectional"))
      (node (ref "R27") (pin "1") (pinfunction "1_1") (pintype "bidirectional"))
      (node (ref "R3") (pin "1") (pinfunction "1_1") (pintype "bidirectional"))
      (node (ref "R31") (pin "1") (pinfunction "1_1") (pintype "bidirectional"))
      (node (ref "R5") (pin "1") (pinfunction "1_1") (pintype "bidirectional"))
      (node (ref "R9") (pin "1") (pinfunction "1_1") (pintype "bidirectional"))
      (node (ref "SPI-LED") (pin "GND") (pinfunction "GND_GND") (pintype "bidirectional"))
      (node (ref "ST") (pin "GND") (pinfunction "GND_GND") (pintype "bidirectional"))
      (node (ref "TH") (pin "GND") (pinfunction "GND_GND") (pintype "bidirectional"))
      (node (ref "U$1") (pin "3") (pinfunction "3:DRAIN_3") (pintype "bidirectional"))
      (node (ref "U$14") (pin "3") (pinfunction "GND_3") (pintype "bidirectional"))
      (node (ref "U$2") (pin "3") (pinfunction "3:DRAIN_3") (pintype "bidirectional"))
      (node (ref "U$3") (pin "3") (pinfunction "3:DRAIN_3") (pintype "bidirectional"))
      (node (ref "U$5") (pin "3") (pinfunction "3:DRAIN_3") (pintype "bidirectional"))
      (node (ref "U$6") (pin "3") (pinfunction "GND_3") (pintype "bidirectional"))
      (node (ref "U$7") (pin "3") (pinfunction "3:DRAIN_3") (pintype "bidirectional"))
      (node (ref "U$8") (pin "3") (pinfunction "3:DRAIN_3") (pintype "bidirectional"))
      (node (ref "U$9") (pin "3") (pinfunction "GND_3") (pintype "bidirectional"))
      (node (ref "U1") (pin "10") (pinfunction "D3_10") (pintype "bidirectional"))
      (node (ref "U1") (pin "14") (pinfunction "E/RD#_14") (pintype "bidirectional"))
      (node (ref "U1") (pin "15") (pinfunction "R/W#_15") (pintype "bidirectional"))
      (node (ref "U1") (pin "16") (pinfunction "D/C#_16") (pintype "bidirectional"))
      (node (ref "U1") (pin "18") (pinfunction "CS#_18") (pintype "bidirectional"))
      (node (ref "U1") (pin "19") (pinfunction "BS2_19") (pintype "bidirectional"))
      (node (ref "U1") (pin "2") (pinfunction "VLSS_2") (pintype "bidirectional"))
      (node (ref "U1") (pin "21") (pinfunction "BS0_21") (pintype "bidirectional"))
      (node (ref "U1") (pin "23") (pinfunction "VSS_23") (pintype "bidirectional"))
      (node (ref "U1") (pin "6") (pinfunction "D7_6") (pintype "bidirectional"))
      (node (ref "U1") (pin "7") (pinfunction "D6_7") (pintype "bidirectional"))
      (node (ref "U1") (pin "8") (pinfunction "D5_8") (pintype "bidirectional"))
      (node (ref "U1") (pin "9") (pinfunction "D4_9") (pintype "bidirectional"))
      (node (ref "X2") (pin "2") (pinfunction "2_2") (pintype "passive"))
    )
    (net (code "48") (name "Net-(C11-Pad2)") (class "Default")
      (node (ref "C11") (pin "2") (pinfunction "2_2") (pintype "passive"))
      (node (ref "D1") (pin "ANODE") (pinfunction "ANODE_ANODE") (pintype "bidirectional"))
      (node (ref "R7") (pin "1") (pinfunction "1_1") (pintype "bidirectional"))
      (node (ref "R8") (pin "2") (pinfunction "2_2") (pintype "bidirectional"))
    )
    (net (code "49") (name "Net-(D2-A)") (class "Default")
      (node (ref "D2") (pin "2") (pinfunction "A_2") (pintype "passive"))
      (node (ref "R21") (pin "1") (pinfunction "1_1") (pintype "bidirectional"))
      (node (ref "U$5") (pin "2") (pinfunction "2:SOURCE_2") (pintype "bidirectional"))
    )
    (net (code "50") (name "Net-(D2-C)") (class "Default")
      (node (ref "D2") (pin "1") (pinfunction "C_1") (pintype "passive"))
      (node (ref "R24") (pin "2") (pinfunction "2_2") (pintype "bidirectional"))
      (node (ref "U$6") (pin "2") (pinfunction "A_2") (pintype "bidirectional"))
    )
    (net (code "51") (name "Net-(D3-A)") (class "Default")
      (node (ref "D3") (pin "2") (pinfunction "A_2") (pintype "passive"))
      (node (ref "R6") (pin "1") (pinfunction "1_1") (pintype "bidirectional"))
      (node (ref "U$2") (pin "2") (pinfunction "2:SOURCE_2") (pintype "bidirectional"))
    )
    (net (code "52") (name "Net-(D3-C)") (class "Default")
      (node (ref "D3") (pin "1") (pinfunction "C_1") (pintype "passive"))
      (node (ref "R27") (pin "2") (pinfunction "2_2") (pintype "bidirectional"))
      (node (ref "U$14") (pin "2") (pinfunction "A_2") (pintype "bidirectional"))
    )
    (net (code "53") (name "Net-(D4-A)") (class "Default")
      (node (ref "D4") (pin "2") (pinfunction "A_2") (pintype "passive"))
      (node (ref "R30") (pin "1") (pinfunction "1_1") (pintype "bidirectional"))
      (node (ref "U$8") (pin "2") (pinfunction "2:SOURCE_2") (pintype "bidirectional"))
    )
    (net (code "54") (name "Net-(D4-C)") (class "Default")
      (node (ref "D4") (pin "1") (pinfunction "C_1") (pintype "passive"))
      (node (ref "R31") (pin "2") (pinfunction "2_2") (pintype "bidirectional"))
      (node (ref "U$9") (pin "2") (pinfunction "A_2") (pintype "bidirectional"))
    )
    (net (code "55") (name "Net-(IC1-AREF)") (class "Default")
      (node (ref "C1") (pin "2") (pinfunction "2_2") (pintype "passive"))
      (node (ref "IC1") (pin "20") (pinfunction "AREF_20") (pintype "bidirectional"))
    )
    (net (code "56") (name "Net-(IC1-PB6(XTAL1{slash}TOSC1))") (class "Default")
      (node (ref "IC1") (pin "7") (pinfunction "PB6(XTAL1/TOSC1)_7") (pintype "bidirectional"))
      (node (ref "X2") (pin "1") (pinfunction "1_1") (pintype "passive"))
    )
    (net (code "57") (name "Net-(IC1-PB7(XTAL2{slash}TOSC2))") (class "Default")
      (node (ref "IC1") (pin "8") (pinfunction "PB7(XTAL2/TOSC2)_8") (pintype "bidirectional"))
      (node (ref "X2") (pin "3") (pinfunction "3_3") (pintype "passive"))
    )
    (net (code "58") (name "Net-(IC4-EXTCLK)") (class "Default")
      (node (ref "IC4") (pin "25") (pinfunction "EXTCLK_25") (pintype "bidirectional"))
      (node (ref "R1") (pin "2") (pinfunction "2_2") (pintype "bidirectional"))
    )
    (net (code "59") (name "Net-(IC4-OE)") (class "Default")
      (node (ref "IC4") (pin "23") (pinfunction "OE_23") (pintype "bidirectional"))
      (node (ref "R3") (pin "2") (pinfunction "2_2") (pintype "bidirectional"))
    )
    (net (code "60") (name "Net-(JETSON-PadCATHODE)") (class "Default")
      (node (ref "JETSON") (pin "CATHODE") (pinfunction "CATHODE_CATHODE") (pintype "passive"))
      (node (ref "R10") (pin "2") (pinfunction "2_2") (pintype "bidirectional"))
    )
    (net (code "61") (name "Net-(JP1-Pad1)") (class "Default")
      (node (ref "JP1") (pin "1") (pinfunction "1_1") (pintype "passive"))
      (node (ref "R12") (pin "1") (pinfunction "1_1") (pintype "bidirectional"))
    )
    (net (code "62") (name "Net-(JP1-Pad2)") (class "Default")
      (node (ref "JP1") (pin "2") (pinfunction "2_2") (pintype "passive"))
      (node (ref "R13") (pin "1") (pinfunction "1_1") (pintype "bidirectional"))
    )
    (net (code "63") (name "Net-(JP2-Pad2)") (class "Default")
      (node (ref "JP2") (pin "2") (pinfunction "2_2") (pintype "passive"))
      (node (ref "R14") (pin "2") (pinfunction "2_2") (pintype "bidirectional"))
      (node (ref "R19") (pin "2") (pinfunction "2_2") (pintype "bidirectional"))
    )
    (net (code "64") (name "Net-(Q1-PadD)") (class "Default")
      (node (ref "Q1") (pin "D") (pinfunction "D_D") (pintype "passive"))
      (node (ref "R17") (pin "2") (pinfunction "2_2") (pintype "bidirectional"))
      (node (ref "R19") (pin "1") (pinfunction "1_1") (pintype "bidirectional"))
    )
    (net (code "65") (name "Net-(Q1-PadG)") (class "Default")
      (node (ref "Q1") (pin "G") (pinfunction "G_G") (pintype "passive"))
      (node (ref "R18") (pin "1") (pinfunction "1_1") (pintype "bidirectional"))
    )
    (net (code "66") (name "Net-(Q2-PadD)") (class "Default")
      (node (ref "Q2") (pin "D") (pinfunction "D_D") (pintype "passive"))
      (node (ref "R14") (pin "1") (pinfunction "1_1") (pintype "bidirectional"))
      (node (ref "R20") (pin "2") (pinfunction "2_2") (pintype "bidirectional"))
    )
    (net (code "67") (name "Net-(Q2-PadG)") (class "Default")
      (node (ref "Q2") (pin "G") (pinfunction "G_G") (pintype "passive"))
      (node (ref "R11") (pin "1") (pinfunction "1_1") (pintype "bidirectional"))
    )
    (net (code "68") (name "Net-(R5-Pad2)") (class "Default")
      (node (ref "R5") (pin "2") (pinfunction "2_2") (pintype "bidirectional"))
      (node (ref "RC") (pin "CATHODE") (pinfunction "CATHODE_CATHODE") (pintype "passive"))
    )
    (net (code "69") (name "Net-(R17-Pad1)") (class "Default")
      (node (ref "R17") (pin "1") (pinfunction "1_1") (pintype "bidirectional"))
      (node (ref "ST") (pin "I/O") (pinfunction "I/O_I/O") (pintype "bidirectional"))
    )
    (net (code "70") (name "Net-(R20-Pad1)") (class "Default")
      (node (ref "R20") (pin "1") (pinfunction "1_1") (pintype "bidirectional"))
      (node (ref "TH") (pin "I/O") (pinfunction "I/O_I/O") (pintype "bidirectional"))
    )
    (net (code "71") (name "Net-(U$1-1:GATE)") (class "Default")
      (node (ref "1") (pin "I/O") (pinfunction "I/O_I/O") (pintype "bidirectional"))
      (node (ref "U$1") (pin "1") (pinfunction "1:GATE_1") (pintype "bidirectional"))
    )
    (net (code "72") (name "Net-(U$1-2:SOURCE)") (class "Default")
      (node (ref "R4") (pin "1") (pinfunction "1_1") (pintype "bidirectional"))
      (node (ref "U$1") (pin "2") (pinfunction "2:SOURCE_2") (pintype "bidirectional"))
      (node (ref "U$2") (pin "1") (pinfunction "1:GATE_1") (pintype "bidirectional"))
    )
    (net (code "73") (name "Net-(U$3-1:GATE)") (class "Default")
      (node (ref "2") (pin "I/O") (pinfunction "I/O_I/O") (pintype "bidirectional"))
      (node (ref "U$3") (pin "1") (pinfunction "1:GATE_1") (pintype "bidirectional"))
    )
    (net (code "74") (name "Net-(U$3-2:SOURCE)") (class "Default")
      (node (ref "R15") (pin "1") (pinfunction "1_1") (pintype "bidirectional"))
      (node (ref "U$3") (pin "2") (pinfunction "2:SOURCE_2") (pintype "bidirectional"))
      (node (ref "U$5") (pin "1") (pinfunction "1:GATE_1") (pintype "bidirectional"))
    )
    (net (code "75") (name "Net-(U$6-Y)") (class "Default")
      (node (ref "R25") (pin "1") (pinfunction "1_1") (pintype "bidirectional"))
      (node (ref "U$6") (pin "4") (pinfunction "Y_4") (pintype "bidirectional"))
    )
    (net (code "76") (name "Net-(U$7-1:GATE)") (class "Default")
      (node (ref "3") (pin "I/O") (pinfunction "I/O_I/O") (pintype "bidirectional"))
      (node (ref "U$7") (pin "1") (pinfunction "1:GATE_1") (pintype "bidirectional"))
    )
    (net (code "77") (name "Net-(U$7-2:SOURCE)") (class "Default")
      (node (ref "R26") (pin "1") (pinfunction "1_1") (pintype "bidirectional"))
      (node (ref "U$7") (pin "2") (pinfunction "2:SOURCE_2") (pintype "bidirectional"))
      (node (ref "U$8") (pin "1") (pinfunction "1:GATE_1") (pintype "bidirectional"))
    )
    (net (code "78") (name "Net-(U$9-Y)") (class "Default")
      (node (ref "R32") (pin "1") (pinfunction "1_1") (pintype "bidirectional"))
      (node (ref "U$9") (pin "4") (pinfunction "Y_4") (pintype "bidirectional"))
    )
    (net (code "79") (name "Net-(U$14-Y)") (class "Default")
      (node (ref "R29") (pin "1") (pinfunction "1_1") (pintype "bidirectional"))
      (node (ref "U$14") (pin "4") (pinfunction "Y_4") (pintype "bidirectional"))
    )
    (net (code "80") (name "Net-(U1-BS1)") (class "Default")
      (node (ref "R28") (pin "1") (pinfunction "1_1") (pintype "bidirectional"))
      (node (ref "U1") (pin "20") (pinfunction "BS1_20") (pintype "bidirectional"))
    )
    (net (code "81") (name "Net-(U1-C1N)") (class "Default")
      (node (ref "C6") (pin "1") (pinfunction "1_1") (pintype "passive"))
      (node (ref "U1") (pin "26") (pinfunction "C1N_26") (pintype "bidirectional"))
    )
    (net (code "82") (name "Net-(U1-C1P)") (class "Default")
      (node (ref "C6") (pin "2") (pinfunction "2_2") (pintype "passive"))
      (node (ref "U1") (pin "27") (pinfunction "C1P_27") (pintype "bidirectional"))
    )
    (net (code "83") (name "Net-(U1-C2N)") (class "Default")
      (node (ref "C5") (pin "1") (pinfunction "1_1") (pintype "passive"))
      (node (ref "U1") (pin "28") (pinfunction "C2N_28") (pintype "bidirectional"))
    )
    (net (code "84") (name "Net-(U1-C2P)") (class "Default")
      (node (ref "C5") (pin "2") (pinfunction "2_2") (pintype "passive"))
      (node (ref "U1") (pin "29") (pinfunction "C2P_29") (pintype "bidirectional"))
    )
    (net (code "85") (name "Net-(U1-IREF)") (class "Default")
      (node (ref "R9") (pin "2") (pinfunction "2_2") (pintype "bidirectional"))
      (node (ref "U1") (pin "5") (pinfunction "IREF_5") (pintype "bidirectional"))
    )
    (net (code "86") (name "Net-(U1-RES#)") (class "Default")
      (node (ref "R8") (pin "1") (pinfunction "1_1") (pintype "bidirectional"))
      (node (ref "U1") (pin "17") (pinfunction "RES#_17") (pintype "bidirectional"))
    )
    (net (code "87") (name "Net-(U1-VCC)") (class "Default")
      (node (ref "C10") (pin "2") (pinfunction "2_2") (pintype "passive"))
      (node (ref "U1") (pin "3") (pinfunction "VCC_3") (pintype "bidirectional"))
    )
    (net (code "88") (name "Net-(U1-VCOMH)") (class "Default")
      (node (ref "C9") (pin "2") (pinfunction "2_2") (pintype "passive"))
      (node (ref "U1") (pin "4") (pinfunction "VCOMH_4") (pintype "bidirectional"))
    )
    (net (code "89") (name "unconnected-(IC1-ADC6-Pad19)") (class "Default")
      (node (ref "IC1") (pin "19") (pinfunction "ADC6_19") (pintype "bidirectional"))
    )
    (net (code "90") (name "unconnected-(IC1-ADC7-Pad22)") (class "Default")
      (node (ref "IC1") (pin "22") (pinfunction "ADC7_22") (pintype "bidirectional"))
    )
    (net (code "91") (name "unconnected-(IC1-PB0(ICP)-Pad12)") (class "Default")
      (node (ref "IC1") (pin "12") (pinfunction "PB0(ICP)_12") (pintype "bidirectional"))
    )
    (net (code "92") (name "unconnected-(IC1-PB1(OC1A)-Pad13)") (class "Default")
      (node (ref "IC1") (pin "13") (pinfunction "PB1(OC1A)_13") (pintype "bidirectional"))
    )
    (net (code "93") (name "unconnected-(IC1-PB2(SS{slash}OC1B)-Pad14)") (class "Default")
      (node (ref "IC1") (pin "14") (pinfunction "PB2(SS/OC1B)_14") (pintype "bidirectional"))
    )
    (net (code "94") (name "unconnected-(IC1-PC2(ADC2)-Pad25)") (class "Default")
      (node (ref "IC1") (pin "25") (pinfunction "PC2(ADC2)_25") (pintype "bidirectional"))
    )
    (net (code "95") (name "unconnected-(IC1-PD5(T1)-Pad9)") (class "Default")
      (node (ref "IC1") (pin "9") (pinfunction "PD5(T1)_9") (pintype "bidirectional"))
    )
    (net (code "96") (name "unconnected-(IC1-PD6(AIN0)-Pad10)") (class "Default")
      (node (ref "IC1") (pin "10") (pinfunction "PD6(AIN0)_10") (pintype "bidirectional"))
    )
    (net (code "97") (name "unconnected-(IC1-PD7(AIN1)-Pad11)") (class "Default")
      (node (ref "IC1") (pin "11") (pinfunction "PD7(AIN1)_11") (pintype "bidirectional"))
    )
    (net (code "98") (name "unconnected-(IC2-CE1-Pad26)") (class "Default")
      (node (ref "IC2") (pin "26") (pinfunction "CE1_26") (pintype "bidirectional"))
    )
    (net (code "99") (name "unconnected-(IC2-ID_SC-Pad28)") (class "Default")
      (node (ref "IC2") (pin "28") (pinfunction "ID_SC_28") (pintype "bidirectional"))
    )
    (net (code "100") (name "unconnected-(IC2-ID_SD-Pad27)") (class "Default")
      (node (ref "IC2") (pin "27") (pinfunction "ID_SD_27") (pintype "bidirectional"))
    )
    (net (code "101") (name "unconnected-(IC3-A2-Pad11)") (class "Default")
      (node (ref "IC3") (pin "11") (pinfunction "A2_11") (pintype "bidirectional"))
    )
    (net (code "102") (name "unconnected-(IC3-A3-Pad14)") (class "Default")
      (node (ref "IC3") (pin "14") (pinfunction "A3_14") (pintype "bidirectional"))
    )
    (net (code "103") (name "unconnected-(IC3-B2-Pad10)") (class "Default")
      (node (ref "IC3") (pin "10") (pinfunction "B2_10") (pintype "bidirectional"))
    )
    (net (code "104") (name "unconnected-(IC3-B3-Pad13)") (class "Default")
      (node (ref "IC3") (pin "13") (pinfunction "B3_13") (pintype "bidirectional"))
    )
    (net (code "105") (name "unconnected-(IC3-Y2-Pad9)") (class "Default")
      (node (ref "IC3") (pin "9") (pinfunction "Y2_9") (pintype "bidirectional"))
    )
    (net (code "106") (name "unconnected-(IC3-Y3-Pad12)") (class "Default")
      (node (ref "IC3") (pin "12") (pinfunction "Y3_12") (pintype "bidirectional"))
    )
    (net (code "107") (name "unconnected-(IC4-LED0-Pad6)") (class "Default")
      (node (ref "IC4") (pin "6") (pinfunction "LED0_6") (pintype "bidirectional"))
    )
    (net (code "108") (name "unconnected-(IC4-LED1-Pad7)") (class "Default")
      (node (ref "IC4") (pin "7") (pinfunction "LED1_7") (pintype "bidirectional"))
    )
    (net (code "109") (name "unconnected-(IC4-LED2-Pad8)") (class "Default")
      (node (ref "IC4") (pin "8") (pinfunction "LED2_8") (pintype "bidirectional"))
    )
    (net (code "110") (name "unconnected-(IC4-LED3-Pad9)") (class "Default")
      (node (ref "IC4") (pin "9") (pinfunction "LED3_9") (pintype "bidirectional"))
    )
    (net (code "111") (name "unconnected-(IC4-LED4-Pad10)") (class "Default")
      (node (ref "IC4") (pin "10") (pinfunction "LED4_10") (pintype "bidirectional"))
    )
    (net (code "112") (name "unconnected-(IC4-LED5-Pad11)") (class "Default")
      (node (ref "IC4") (pin "11") (pinfunction "LED5_11") (pintype "bidirectional"))
    )
    (net (code "113") (name "unconnected-(IC4-LED6-Pad12)") (class "Default")
      (node (ref "IC4") (pin "12") (pinfunction "LED6_12") (pintype "bidirectional"))
    )
    (net (code "114") (name "unconnected-(IC4-LED7-Pad13)") (class "Default")
      (node (ref "IC4") (pin "13") (pinfunction "LED7_13") (pintype "bidirectional"))
    )
    (net (code "115") (name "unconnected-(IC4-LED8-Pad15)") (class "Default")
      (node (ref "IC4") (pin "15") (pinfunction "LED8_15") (pintype "bidirectional"))
    )
    (net (code "116") (name "unconnected-(IC4-LED9-Pad16)") (class "Default")
      (node (ref "IC4") (pin "16") (pinfunction "LED9_16") (pintype "bidirectional"))
    )
    (net (code "117") (name "unconnected-(IC4-LED10-Pad17)") (class "Default")
      (node (ref "IC4") (pin "17") (pinfunction "LED10_17") (pintype "bidirectional"))
    )
    (net (code "118") (name "unconnected-(IC4-LED11-Pad18)") (class "Default")
      (node (ref "IC4") (pin "18") (pinfunction "LED11_18") (pintype "bidirectional"))
    )
    (net (code "119") (name "unconnected-(IC4-LED12-Pad19)") (class "Default")
      (node (ref "IC4") (pin "19") (pinfunction "LED12_19") (pintype "bidirectional"))
    )
    (net (code "120") (name "unconnected-(IC4-LED13-Pad20)") (class "Default")
      (node (ref "IC4") (pin "20") (pinfunction "LED13_20") (pintype "bidirectional"))
    )
    (net (code "121") (name "unconnected-(IC4-LED14-Pad21)") (class "Default")
      (node (ref "IC4") (pin "21") (pinfunction "LED14_21") (pintype "bidirectional"))
    )
    (net (code "122") (name "unconnected-(IC4-LED15-Pad22)") (class "Default")
      (node (ref "IC4") (pin "22") (pinfunction "LED15_22") (pintype "bidirectional"))
    )
    (net (code "123") (name "unconnected-(U1-NC-Pad1)") (class "Default")
      (node (ref "U1") (pin "1") (pinfunction "NC_1") (pintype "bidirectional"))
    )
    (net (code "124") (name "unconnected-(U1-NC-Pad24)") (class "Default")
      (node (ref "U1") (pin "24") (pinfunction "NC_24") (pintype "bidirectional"))
    )
    (net (code "125") (name "unconnected-(U1-NC-Pad30)") (class "Default")
      (node (ref "U1") (pin "30") (pinfunction "NC_30") (pintype "bidirectional"))
    )
  )
)
